# design.net
KiCad netlist of a schematic drawn in Altium Designer
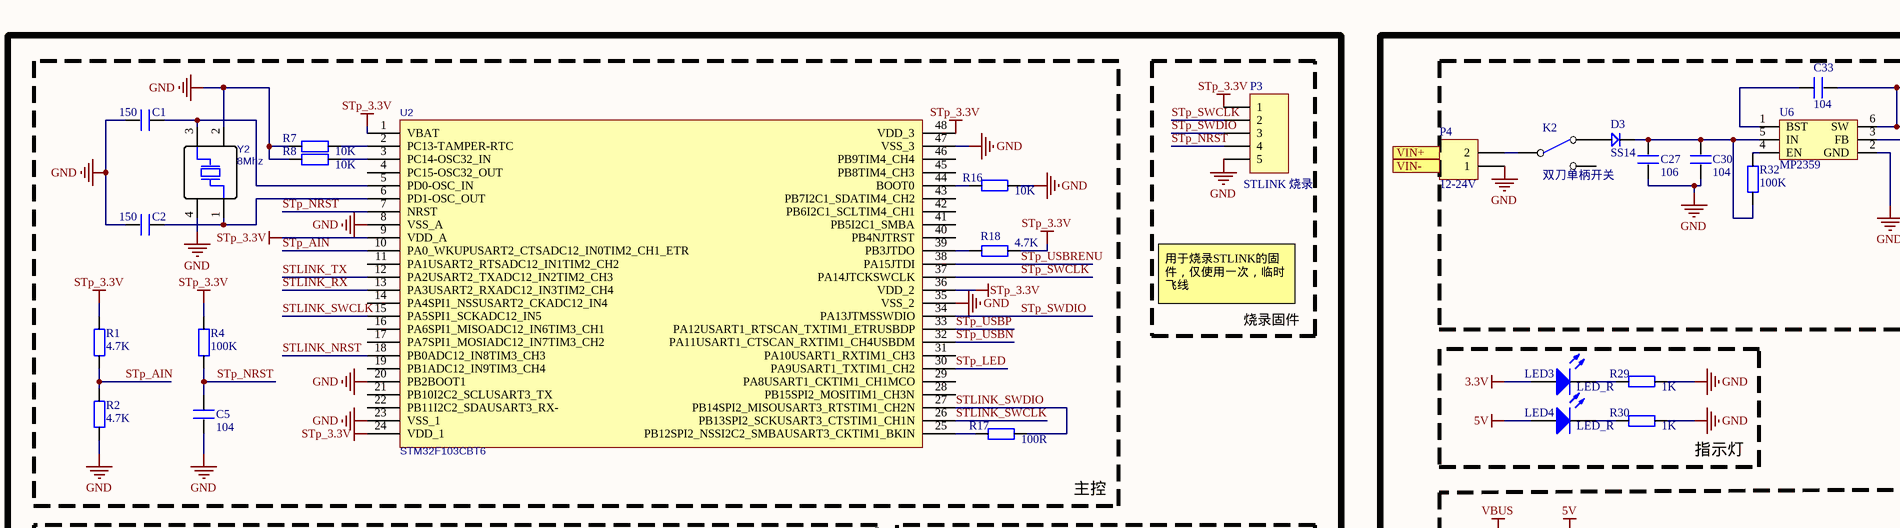
[diagram p0: 主板.SchDoc, top left]
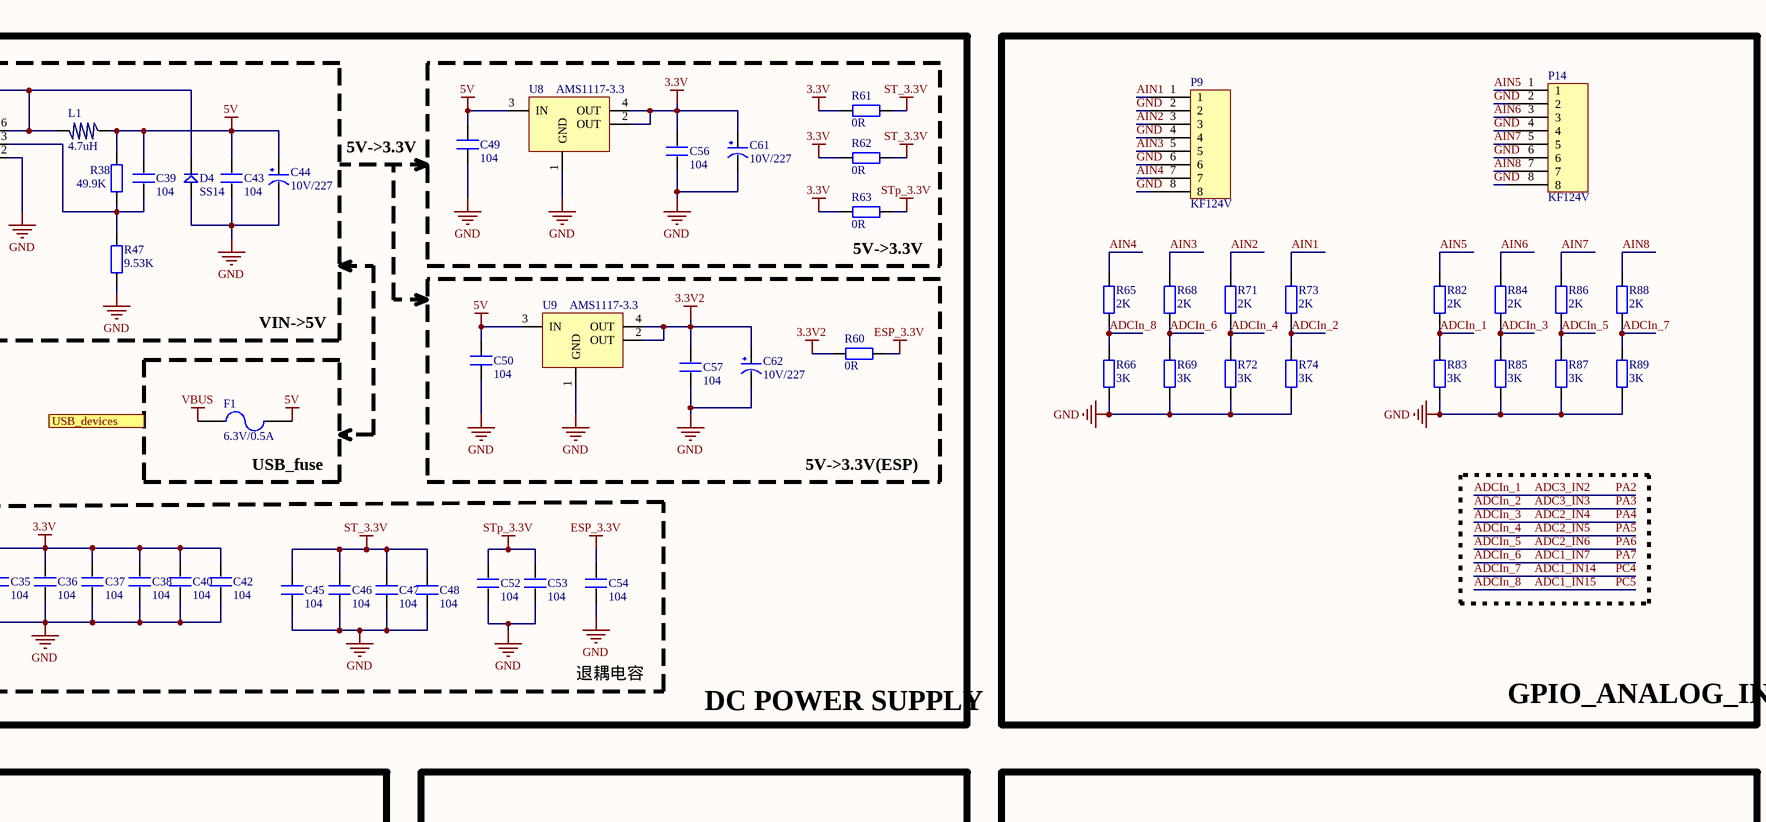
[diagram p1: 主板.SchDoc, top right]
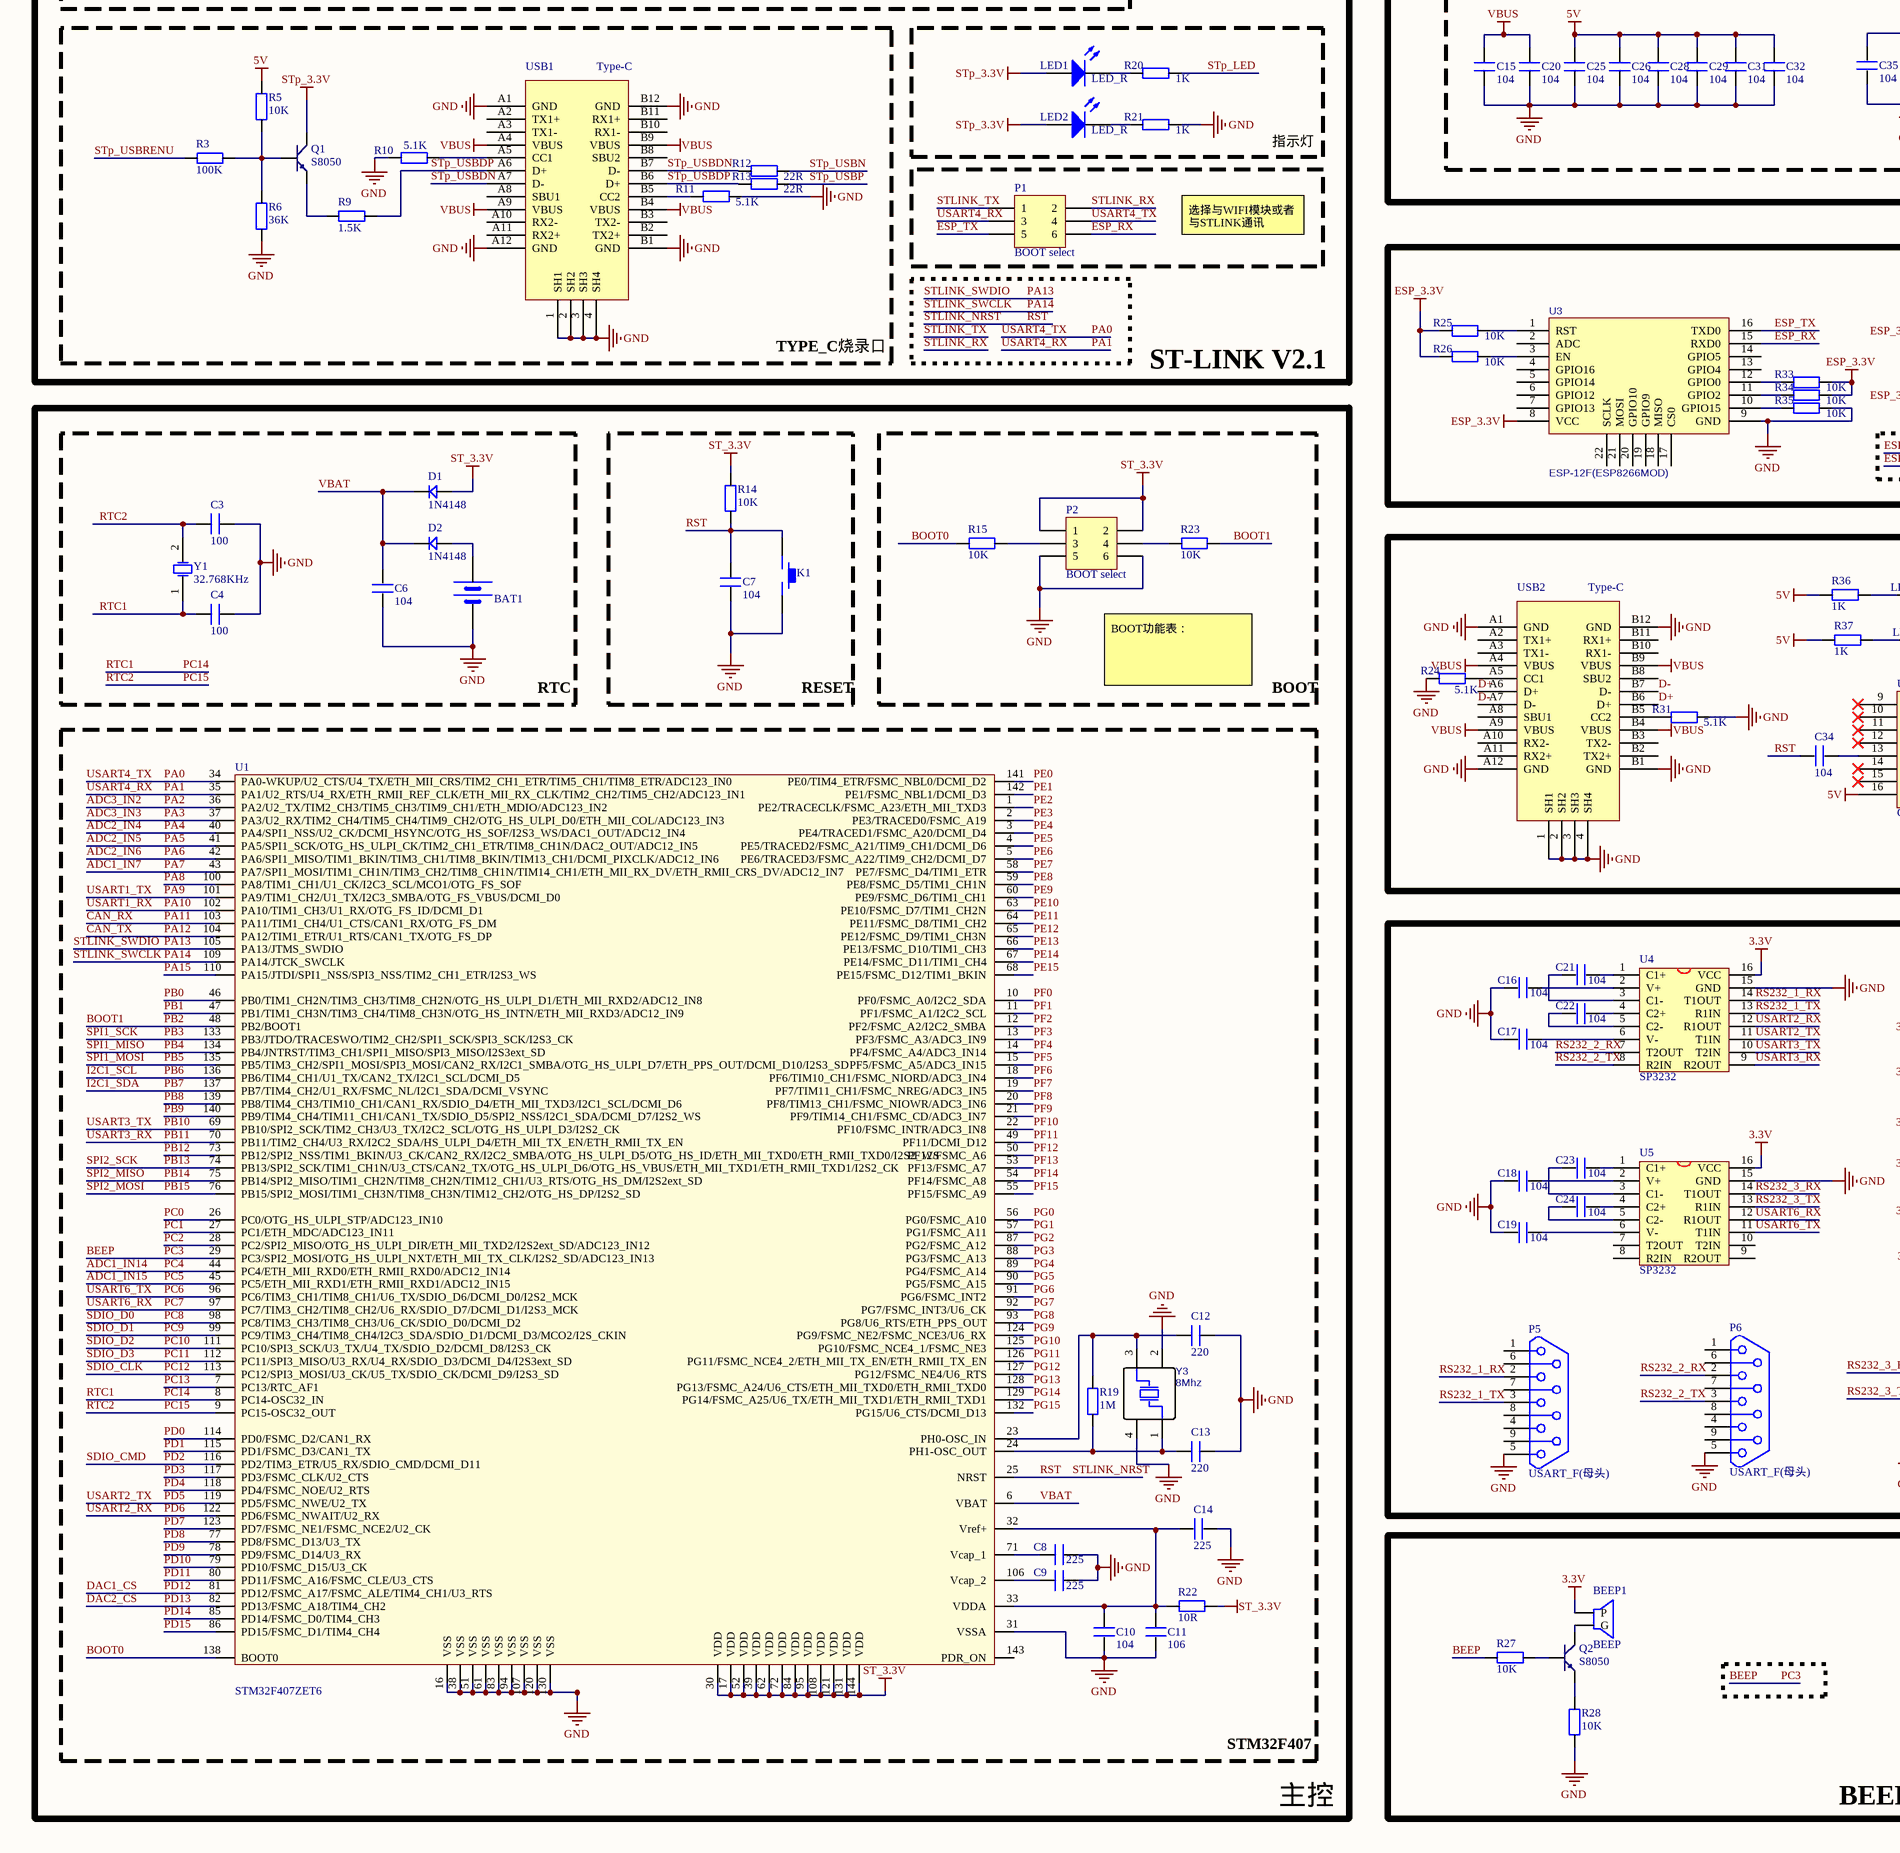
[diagram p2: 主板.SchDoc, bottom left]
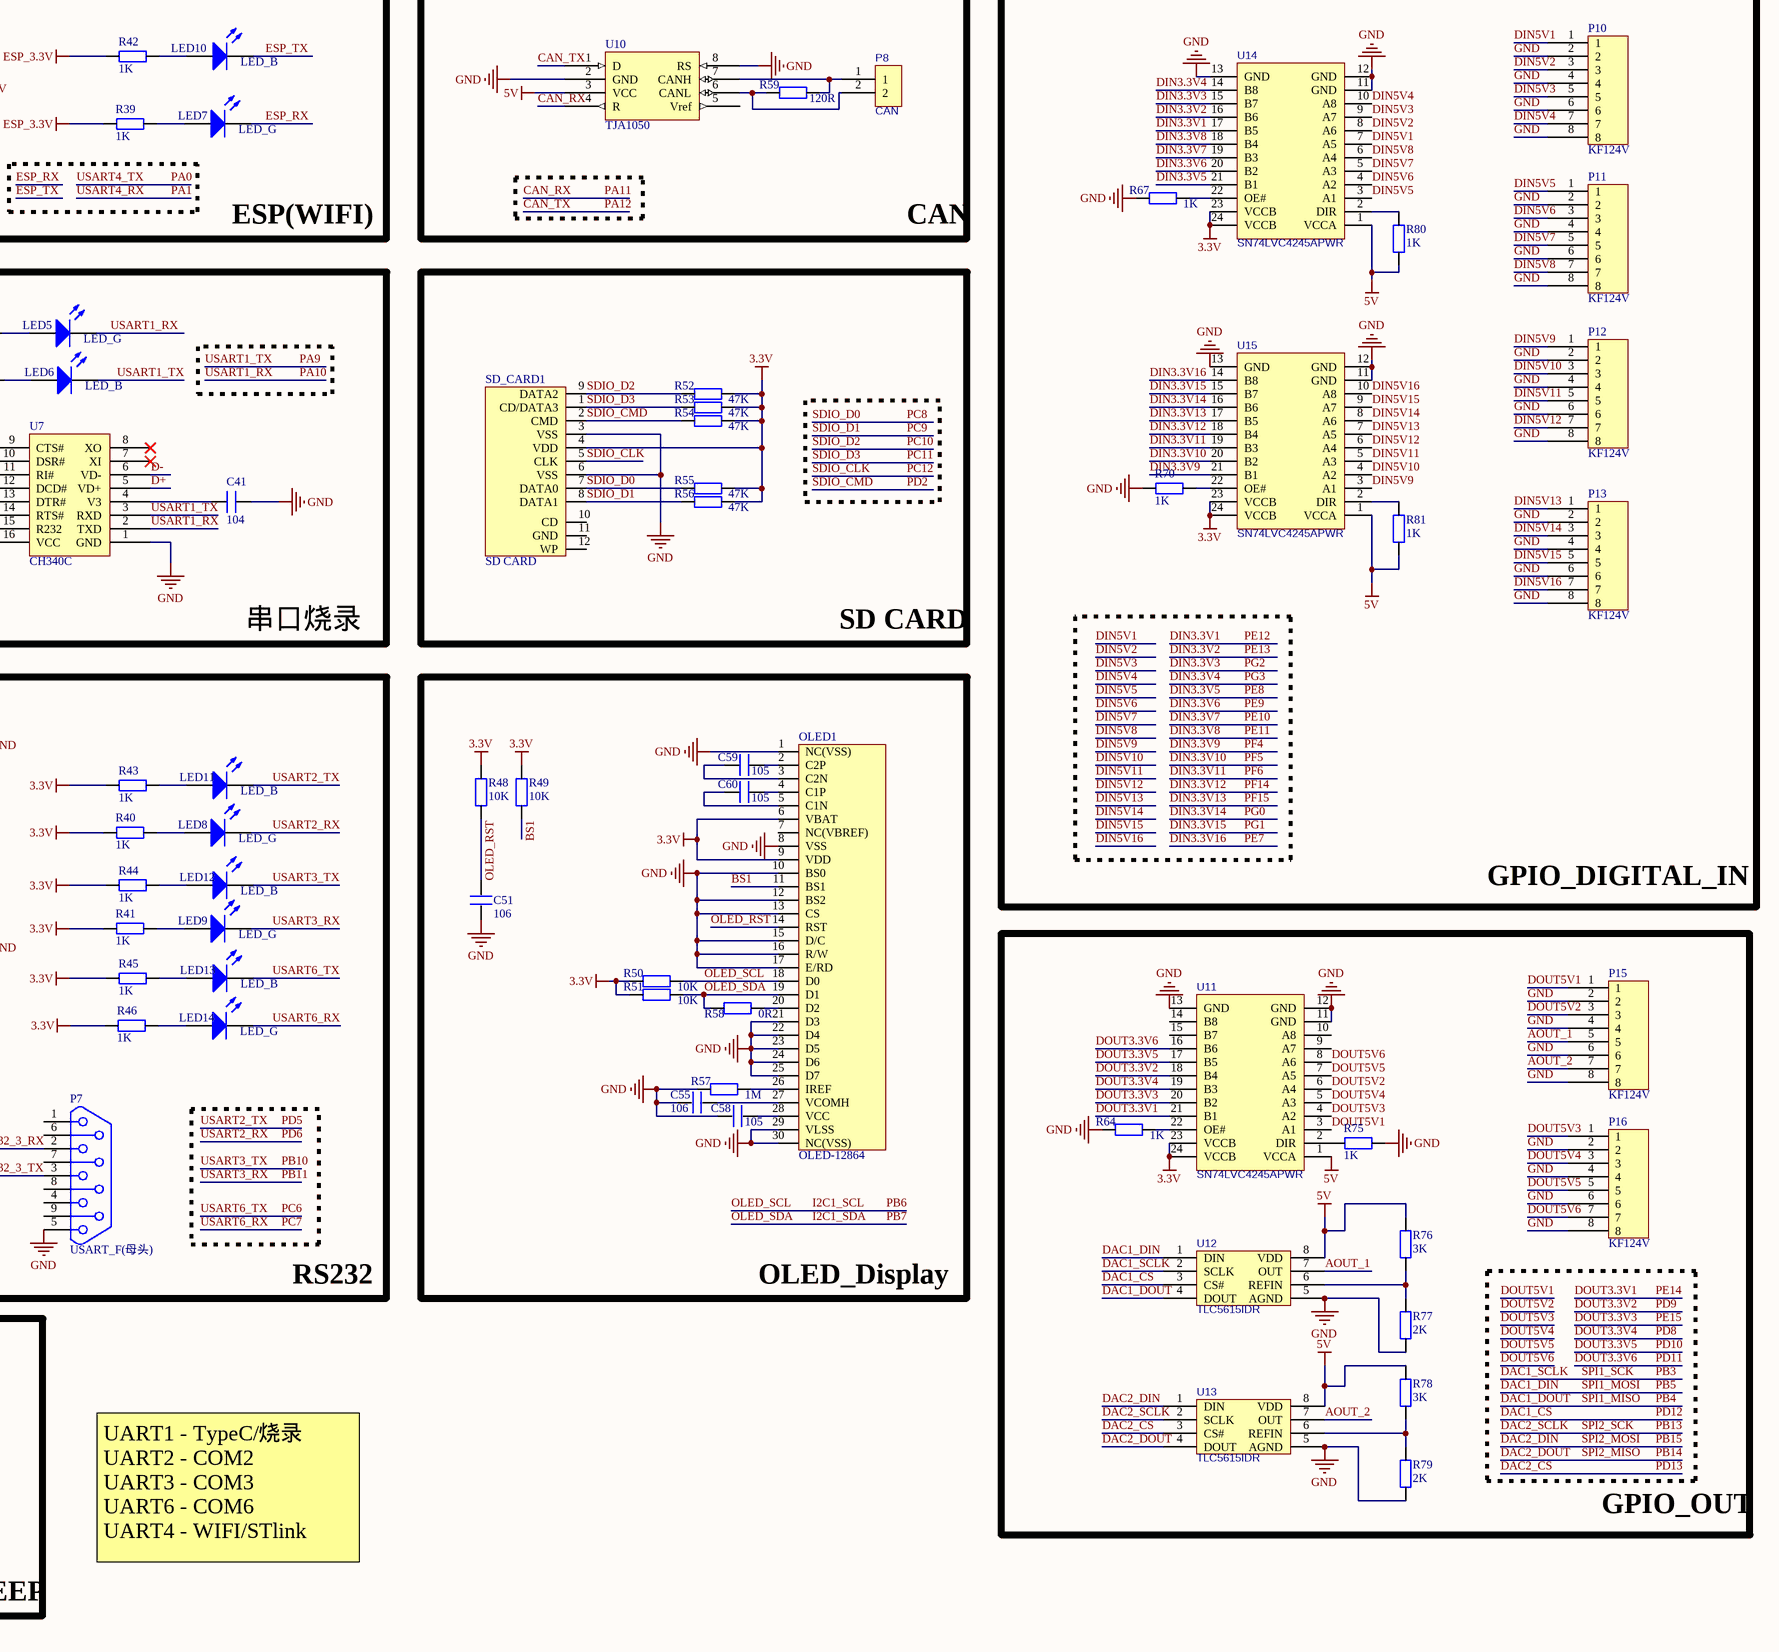
[diagram p3: 主板.SchDoc, bottom right]

(export (version "E")
  (design (tool "Eeschema 10.0.6"))
  (components
    (comp (ref "BAT1") (value "BATT") (footprint "CR1220_B") (libsource (lib "EXPLORER") (part "BAT")))
    (comp (ref "BEEP1") (value "BEEP") (footprint "BEEP 5x9x5.5") (libsource (lib "EXPLORER") (part "BEEP")))
    (comp (ref "C1") (value "150") (footprint "C 0805_L") (libsource (lib "EXPLORER") (part "C")))
    (comp (ref "C2") (value "150") (footprint "C 0805_L") (libsource (lib "EXPLORER") (part "C")))
    (comp (ref "C3") (value "100") (footprint "C 0805_L") (libsource (lib "EXPLORER") (part "C")))
    (comp (ref "C4") (value "100") (footprint "C 0805_L") (libsource (lib "EXPLORER") (part "C")))
    (comp (ref "C5") (value "104") (footprint "C 0805_L") (libsource (lib "EXPLORER") (part "C")))
    (comp (ref "C6") (value "104") (footprint "C 0805_L") (libsource (lib "EXPLORER") (part "C")))
    (comp (ref "C7") (value "104") (footprint "C 0805_L") (libsource (lib "EXPLORER") (part "C")))
    (comp (ref "C8") (value "225") (footprint "C 0805_L") (libsource (lib "EXPLORER") (part "C")))
    (comp (ref "C9") (value "225") (footprint "C 0805_L") (libsource (lib "EXPLORER") (part "C")))
    (comp (ref "C10") (value "104") (footprint "C 0805_L") (libsource (lib "EXPLORER") (part "C")))
    (comp (ref "C11") (value "106") (footprint "C 0805_L") (libsource (lib "EXPLORER") (part "C")))
    (comp (ref "C12") (value "220") (footprint "C 0805_L") (libsource (lib "EXPLORER") (part "C")))
    (comp (ref "C13") (value "220") (footprint "C 0805_L") (libsource (lib "EXPLORER") (part "C")))
    (comp (ref "C14") (value "225") (footprint "C 0805_L") (libsource (lib "EXPLORER") (part "C")))
    (comp (ref "C15") (value "104") (footprint "C 0805_L") (libsource (lib "EXPLORER") (part "C")))
    (comp (ref "C16") (value "104") (footprint "C 0805_L") (libsource (lib "EXPLORER") (part "C")))
    (comp (ref "C17") (value "104") (footprint "C 0805_L") (libsource (lib "EXPLORER") (part "C")))
    (comp (ref "C18") (value "104") (footprint "C 0805_L") (libsource (lib "EXPLORER") (part "C")))
    (comp (ref "C19") (value "104") (footprint "C 0805_L") (libsource (lib "EXPLORER") (part "C")))
    (comp (ref "C20") (value "104") (footprint "C 0805_L") (libsource (lib "EXPLORER") (part "C")))
    (comp (ref "C21") (value "104") (footprint "C 0805_L") (libsource (lib "EXPLORER") (part "C")))
    (comp (ref "C22") (value "104") (footprint "C 0805_L") (libsource (lib "EXPLORER") (part "C")))
    (comp (ref "C23") (value "104") (footprint "C 0805_L") (libsource (lib "EXPLORER") (part "C")))
    (comp (ref "C24") (value "104") (footprint "C 0805_L") (libsource (lib "EXPLORER") (part "C")))
    (comp (ref "C25") (value "104") (footprint "C 0805_L") (libsource (lib "EXPLORER") (part "C")))
    (comp (ref "C26") (value "104") (footprint "C 0805_L") (libsource (lib "EXPLORER") (part "C")))
    (comp (ref "C27") (value "106") (footprint "C 1206_L") (libsource (lib "EXPLORER") (part "C")))
    (comp (ref "C28") (value "104") (footprint "C 0805_L") (libsource (lib "EXPLORER") (part "C")))
    (comp (ref "C29") (value "104") (footprint "C 0805_L") (libsource (lib "EXPLORER") (part "C")))
    (comp (ref "C30") (value "104") (footprint "C 0805_L") (libsource (lib "EXPLORER") (part "C")))
    (comp (ref "C31") (value "104") (footprint "C 0805_L") (libsource (lib "EXPLORER") (part "C")))
    (comp (ref "C32") (value "104") (footprint "C 0805_L") (libsource (lib "EXPLORER") (part "C")))
    (comp (ref "C33") (value "104") (footprint "C 0805_L") (libsource (lib "EXPLORER") (part "C")))
    (comp (ref "C34")
      (value "104")
      (footprint "C 0805_L")
      (description "（可去）")
      (libsource (lib "EXPLORER") (part "C"))
    )
    (comp (ref "C35") (value "104") (footprint "C 0805_L") (libsource (lib "EXPLORER") (part "C")))
    (comp (ref "C36") (value "104") (footprint "C 0805_L") (libsource (lib "EXPLORER") (part "C")))
    (comp (ref "C37") (value "104") (footprint "C 0805_L") (libsource (lib "EXPLORER") (part "C")))
    (comp (ref "C38") (value "104") (footprint "C 0805_L") (libsource (lib "EXPLORER") (part "C")))
    (comp (ref "C39") (value "104") (footprint "C 0805_L") (libsource (lib "EXPLORER") (part "C")))
    (comp (ref "C40") (value "104") (footprint "C 0805_L") (libsource (lib "EXPLORER") (part "C")))
    (comp (ref "C41") (value "104") (footprint "C 0805_L") (libsource (lib "EXPLORER") (part "C")))
    (comp (ref "C42") (value "104") (footprint "C 0805_L") (libsource (lib "EXPLORER") (part "C")))
    (comp (ref "C43") (value "104") (footprint "C 0805_L") (libsource (lib "EXPLORER") (part "C")))
    (comp (ref "C44") (value "10V/227") (footprint "CM D(6.3*7.7)") (libsource (lib "EXPLORER") (part "CAP")))
    (comp (ref "C45") (value "104") (footprint "C 0805_L") (libsource (lib "EXPLORER") (part "C")))
    (comp (ref "C46") (value "104") (footprint "C 0805_L") (libsource (lib "EXPLORER") (part "C")))
    (comp (ref "C47") (value "104") (footprint "C 0805_L") (libsource (lib "EXPLORER") (part "C")))
    (comp (ref "C48") (value "104") (footprint "C 0805_L") (libsource (lib "EXPLORER") (part "C")))
    (comp (ref "C49") (value "104") (footprint "C 0805_L") (libsource (lib "EXPLORER") (part "C")))
    (comp (ref "C50") (value "104") (footprint "C 0805_L") (libsource (lib "EXPLORER") (part "C")))
    (comp (ref "C51") (value "106") (footprint "C 0805_L") (libsource (lib "EXPLORER") (part "C")))
    (comp (ref "C52") (value "104") (footprint "C 0805_L") (libsource (lib "EXPLORER") (part "C")))
    (comp (ref "C53") (value "104") (footprint "C 0805_L") (libsource (lib "EXPLORER") (part "C")))
    (comp (ref "C54") (value "104") (footprint "C 0805_L") (libsource (lib "EXPLORER") (part "C")))
    (comp (ref "C55") (value "106") (footprint "C 0805_L") (libsource (lib "EXPLORER") (part "C")))
    (comp (ref "C56") (value "104") (footprint "C 0805_L") (libsource (lib "EXPLORER") (part "C")))
    (comp (ref "C57") (value "104") (footprint "C 0805_L") (libsource (lib "EXPLORER") (part "C")))
    (comp (ref "C58") (value "105") (footprint "C 0805_L") (libsource (lib "EXPLORER") (part "C")))
    (comp (ref "C59") (value "105") (footprint "C 0805_L") (libsource (lib "EXPLORER") (part "C")))
    (comp (ref "C60") (value "105") (footprint "C 0805_L") (libsource (lib "EXPLORER") (part "C")))
    (comp (ref "C61") (value "10V/227") (footprint "CM D(6.3*7.7)") (libsource (lib "EXPLORER") (part "CAP")))
    (comp (ref "C62") (value "10V/227") (footprint "CM D(6.3*7.7)") (libsource (lib "EXPLORER") (part "CAP")))
    (comp (ref "D1") (value "1N4148") (footprint "MINI_MELF (LL34)") (libsource (lib "EXPLORER") (part "D")))
    (comp (ref "D2") (value "1N4148") (footprint "MINI_MELF (LL34)") (libsource (lib "EXPLORER") (part "D")))
    (comp (ref "D3") (value "SS14") (footprint "SMA") (libsource (lib "EXPLORER") (part "D")))
    (comp (ref "D4") (value "SS14") (footprint "SMA") (libsource (lib "EXPLORER") (part "D")))
    (comp (ref "F1")
      (value "6.3V/0.5A")
      (footprint "C 0805_L")
      (description "Fuse")
      (fields (field (name "PUBLISHER") "Altium Limited"))
      (libsource (lib "Miscellaneous Devices") (part "Fuse 2"))
    )
    (comp (ref "K1")
      (value "KEY_M")
      (footprint "TSW SMD-3*6*2.5")
      (libsource (lib "EXPLORER") (part "KEY_M"))
    )
    (comp (ref "K2") (value "双刀单柄开关") (footprint "SS-12D10") (libsource (lib "k-开关") (part "双刀单柄开关")))
    (comp (ref "L1") (value "4.7uH") (footprint "CDRH74") (libsource (lib "EXPLORER") (part "L")))
    (comp (ref "LED1")
      (value "LED_R")
      (footprint "LED 0805R")
      (description "Typical RED, GREEN, YELLOW, AMBER GaAs LED")
      (fields (field (name "PUBLISHER") "Altium Limited"))
      (libsource (lib "EXPLORER") (part "LED"))
    )
    (comp (ref "LED2")
      (value "LED_R")
      (footprint "LED 0805R")
      (description "Typical RED, GREEN, YELLOW, AMBER GaAs LED")
      (fields (field (name "PUBLISHER") "Altium Limited"))
      (libsource (lib "EXPLORER") (part "LED"))
    )
    (comp (ref "LED3")
      (value "LED_R")
      (footprint "LED 0805R")
      (description "Typical RED, GREEN, YELLOW, AMBER GaAs LED")
      (fields (field (name "PUBLISHER") "Altium Limited"))
      (libsource (lib "EXPLORER") (part "LED"))
    )
    (comp (ref "LED4")
      (value "LED_R")
      (footprint "LED 0805R")
      (description "Typical RED, GREEN, YELLOW, AMBER GaAs LED")
      (fields (field (name "PUBLISHER") "Altium Limited"))
      (libsource (lib "EXPLORER") (part "LED"))
    )
    (comp (ref "LED5")
      (value "LED_G")
      (footprint "LED 0805G")
      (description "Typical RED, GREEN, YELLOW, AMBER GaAs LED")
      (fields (field (name "PUBLISHER") "Altium Limited"))
      (libsource (lib "EXPLORER") (part "LED"))
    )
    (comp (ref "LED6")
      (value "LED_B")
      (footprint "LED 0805B")
      (description "Typical RED, GREEN, YELLOW, AMBER GaAs LED")
      (fields (field (name "PUBLISHER") "Altium Limited"))
      (libsource (lib "EXPLORER") (part "LED"))
    )
    (comp (ref "LED7")
      (value "LED_G")
      (footprint "LED 0805G")
      (description "Typical RED, GREEN, YELLOW, AMBER GaAs LED")
      (fields (field (name "PUBLISHER") "Altium Limited"))
      (libsource (lib "EXPLORER") (part "LED"))
    )
    (comp (ref "LED8")
      (value "LED_G")
      (footprint "LED 0805G")
      (description "Typical RED, GREEN, YELLOW, AMBER GaAs LED")
      (fields (field (name "PUBLISHER") "Altium Limited"))
      (libsource (lib "EXPLORER") (part "LED"))
    )
    (comp (ref "LED9")
      (value "LED_G")
      (footprint "LED 0805G")
      (description "Typical RED, GREEN, YELLOW, AMBER GaAs LED")
      (fields (field (name "PUBLISHER") "Altium Limited"))
      (libsource (lib "EXPLORER") (part "LED"))
    )
    (comp (ref "LED10")
      (value "LED_B")
      (footprint "LED 0805B")
      (description "Typical RED, GREEN, YELLOW, AMBER GaAs LED")
      (fields (field (name "PUBLISHER") "Altium Limited"))
      (libsource (lib "EXPLORER") (part "LED"))
    )
    (comp (ref "LED11")
      (value "LED_B")
      (footprint "LED 0805B")
      (description "Typical RED, GREEN, YELLOW, AMBER GaAs LED")
      (fields (field (name "PUBLISHER") "Altium Limited"))
      (libsource (lib "EXPLORER") (part "LED"))
    )
    (comp (ref "LED12")
      (value "LED_B")
      (footprint "LED 0805B")
      (description "Typical RED, GREEN, YELLOW, AMBER GaAs LED")
      (fields (field (name "PUBLISHER") "Altium Limited"))
      (libsource (lib "EXPLORER") (part "LED"))
    )
    (comp (ref "LED13")
      (value "LED_B")
      (footprint "LED 0805B")
      (description "Typical RED, GREEN, YELLOW, AMBER GaAs LED")
      (fields (field (name "PUBLISHER") "Altium Limited"))
      (libsource (lib "EXPLORER") (part "LED"))
    )
    (comp (ref "LED14")
      (value "LED_G")
      (footprint "LED 0805G")
      (description "Typical RED, GREEN, YELLOW, AMBER GaAs LED")
      (fields (field (name "PUBLISHER") "Altium Limited"))
      (libsource (lib "EXPLORER") (part "LED"))
    )
    (comp (ref "OLED1")
      (value "OLED-12864")
      (footprint "OLED-12864-1.3-TOP")
      (description "显示屏")
      (libsource (lib "EXPLORER") (part "OLED-12864"))
    )
    (comp (ref "P1")
      (value "BOOT select")
      (footprint "HDR2.54-LI-2x3P")
      (description "Header, 3-Pin, Dual row")
      (fields (field (name "PUBLISHER") "Altium Limited"))
      (libsource (lib "EXPLORER") (part "Header 3X2"))
    )
    (comp (ref "P2")
      (value "BOOT select")
      (footprint "HDR2.54-LI-2x3P")
      (description "Header, 3-Pin, Dual row")
      (fields (field (name "PUBLISHER") "Altium Limited"))
      (libsource (lib "EXPLORER") (part "Header 3X2"))
    )
    (comp (ref "P3")
      (value "STLINK 烧录")
      (footprint "ISP5")
      (description "Header, 5-Pin")
      (fields (field (name "PUBLISHER") "Altium Limited"))
      (libsource (lib "主板") (part "Header 5"))
    )
    (comp (ref "P4")
      (value "12-24V")
      (footprint "KF128-5.08-2P")
      (fields (field (name "PUBLISHER") "Altium Limited"))
      (libsource (lib "EXPLORER") (part "Header 2"))
    )
    (comp (ref "P5") (value "USART_F(母头)") (footprint "DB9/S_A") (libsource (lib "EXPLORER") (part "DB9母头")))
    (comp (ref "P6") (value "USART_F(母头)") (footprint "DB9/S_A") (libsource (lib "EXPLORER") (part "DB9母头")))
    (comp (ref "P7") (value "USART_F(母头)") (footprint "DB9/S_A") (libsource (lib "EXPLORER") (part "DB9母头")))
    (comp (ref "P8")
      (value "CAN")
      (footprint "KF142V-5.08-2P")
      (fields
        (field (name "BOM_SUPPLIER PART") "C475134")
        (field (name "BOM_MANUFACTURER PART") "KF142V-5.08-2P")
        (field (name "CONTRIBUTOR") "LCSC")
      )
      (libsource (lib "EXPLORER") (part "KF142V-2P"))
    )
    (comp (ref "P9") (value "KF124V") (footprint "KF142V-5.08-8P") (libsource (lib "EXPLORER") (part "KF8P")))
    (comp (ref "P10")
      (value "KF124V")
      (footprint "KF142V-5.08-8P")
      (libsource (lib "EXPLORER") (part "KF142V-8P"))
    )
    (comp (ref "P11")
      (value "KF124V")
      (footprint "KF142V-5.08-8P")
      (libsource (lib "EXPLORER") (part "KF142V-8P"))
    )
    (comp (ref "P12")
      (value "KF124V")
      (footprint "KF142V-5.08-8P")
      (libsource (lib "EXPLORER") (part "KF142V-8P"))
    )
    (comp (ref "P13")
      (value "KF124V")
      (footprint "KF142V-5.08-8P")
      (libsource (lib "EXPLORER") (part "KF142V-8P"))
    )
    (comp (ref "P14")
      (value "KF124V")
      (footprint "KF142V-5.08-8P")
      (libsource (lib "EXPLORER") (part "KF142V-8P"))
    )
    (comp (ref "P15")
      (value "KF124V")
      (footprint "KF142V-5.08-8P")
      (libsource (lib "EXPLORER") (part "KF142V-8P"))
    )
    (comp (ref "P16")
      (value "KF124V")
      (footprint "KF142V-5.08-8P")
      (libsource (lib "EXPLORER") (part "KF142V-8P"))
    )
    (comp (ref "Q1")
      (value "S8050")
      (footprint "SOT23-3L")
      (description "8050/BCW846/BCW847")
      (libsource (lib "EXPLORER") (part "NPN"))
    )
    (comp (ref "Q2")
      (value "S8050")
      (footprint "SOT23-3L")
      (description "8050/BCW846/BCW847")
      (libsource (lib "EXPLORER") (part "NPN"))
    )
    (comp (ref "R1") (value "4.7K") (footprint "R 0805_L") (libsource (lib "EXPLORER") (part "R")))
    (comp (ref "R2") (value "4.7K") (footprint "R 0805_L") (libsource (lib "EXPLORER") (part "R")))
    (comp (ref "R3") (value "100K") (footprint "R 0805_L") (libsource (lib "EXPLORER") (part "R")))
    (comp (ref "R4") (value "100K") (footprint "R 0805_L") (libsource (lib "EXPLORER") (part "R")))
    (comp (ref "R5") (value "10K") (footprint "R 0805_L") (libsource (lib "EXPLORER") (part "R")))
    (comp (ref "R6") (value "36K") (footprint "R 0805_L") (libsource (lib "EXPLORER") (part "R")))
    (comp (ref "R7") (value "10K") (footprint "R 0805_L") (libsource (lib "EXPLORER") (part "R")))
    (comp (ref "R8") (value "10K") (footprint "R 0805_L") (libsource (lib "EXPLORER") (part "R")))
    (comp (ref "R9") (value "1.5K") (footprint "R 0805_L") (libsource (lib "EXPLORER") (part "R")))
    (comp (ref "R10") (value "5.1K") (footprint "R 0805_L") (libsource (lib "EXPLORER") (part "R")))
    (comp (ref "R11") (value "5.1K") (footprint "R 0805_L") (libsource (lib "EXPLORER") (part "R")))
    (comp (ref "R12") (value "22R") (footprint "R 0805_L") (libsource (lib "EXPLORER") (part "R")))
    (comp (ref "R13") (value "22R") (footprint "R 0805_L") (libsource (lib "EXPLORER") (part "R")))
    (comp (ref "R14") (value "10K") (footprint "R 0805_L") (libsource (lib "EXPLORER") (part "R")))
    (comp (ref "R15") (value "10K") (footprint "R 0805_L") (libsource (lib "EXPLORER") (part "R")))
    (comp (ref "R16") (value "10K") (footprint "R 0805_L") (libsource (lib "EXPLORER") (part "R")))
    (comp (ref "R17") (value "100R") (footprint "R 0805_L") (libsource (lib "EXPLORER") (part "R")))
    (comp (ref "R18") (value "4.7K") (footprint "R 0805_L") (libsource (lib "EXPLORER") (part "R")))
    (comp (ref "R19") (value "1M") (footprint "R 0805_L") (libsource (lib "EXPLORER") (part "R")))
    (comp (ref "R20") (value "1K") (footprint "R 0805_L") (libsource (lib "EXPLORER") (part "R")))
    (comp (ref "R21") (value "1K") (footprint "R 0805_L") (libsource (lib "EXPLORER") (part "R")))
    (comp (ref "R22") (value "10R") (footprint "R 0805_L") (libsource (lib "EXPLORER") (part "R")))
    (comp (ref "R23") (value "10K") (footprint "R 0805_L") (libsource (lib "EXPLORER") (part "R")))
    (comp (ref "R24") (value "5.1K") (footprint "R 0805_L") (libsource (lib "EXPLORER") (part "R")))
    (comp (ref "R25") (value "10K") (footprint "R 0805_L") (libsource (lib "EXPLORER") (part "R")))
    (comp (ref "R26") (value "10K") (footprint "R 0805_L") (libsource (lib "EXPLORER") (part "R")))
    (comp (ref "R27") (value "10K") (footprint "R 0805_L") (libsource (lib "EXPLORER") (part "R")))
    (comp (ref "R28") (value "10K") (footprint "R 0805_L") (libsource (lib "EXPLORER") (part "R")))
    (comp (ref "R29") (value "1K") (footprint "R 0805_L") (libsource (lib "EXPLORER") (part "R")))
    (comp (ref "R30") (value "1K") (footprint "R 0805_L") (libsource (lib "EXPLORER") (part "R")))
    (comp (ref "R31") (value "5.1K") (footprint "R 0805_L") (libsource (lib "EXPLORER") (part "R")))
    (comp (ref "R32") (value "100K") (footprint "R 0805_L") (libsource (lib "EXPLORER") (part "R")))
    (comp (ref "R33") (value "10K") (footprint "R 0805_L") (libsource (lib "EXPLORER") (part "R")))
    (comp (ref "R34") (value "10K") (footprint "R 0805_L") (libsource (lib "EXPLORER") (part "R")))
    (comp (ref "R35") (value "10K") (footprint "R 0805_L") (libsource (lib "EXPLORER") (part "R")))
    (comp (ref "R36") (value "1K") (footprint "R 0805_L") (libsource (lib "EXPLORER") (part "R")))
    (comp (ref "R37") (value "1K") (footprint "R 0805_L") (libsource (lib "EXPLORER") (part "R")))
    (comp (ref "R38") (value "49.9K") (footprint "R 0805_L") (libsource (lib "EXPLORER") (part "R")))
    (comp (ref "R39") (value "1K") (footprint "R 0805_L") (libsource (lib "EXPLORER") (part "R")))
    (comp (ref "R40") (value "1K") (footprint "R 0805_L") (libsource (lib "EXPLORER") (part "R")))
    (comp (ref "R41") (value "1K") (footprint "R 0805_L") (libsource (lib "EXPLORER") (part "R")))
    (comp (ref "R42") (value "1K") (footprint "R 0805_L") (libsource (lib "EXPLORER") (part "R")))
    (comp (ref "R43") (value "1K") (footprint "R 0805_L") (libsource (lib "EXPLORER") (part "R")))
    (comp (ref "R44") (value "1K") (footprint "R 0805_L") (libsource (lib "EXPLORER") (part "R")))
    (comp (ref "R45") (value "1K") (footprint "R 0805_L") (libsource (lib "EXPLORER") (part "R")))
    (comp (ref "R46") (value "1K") (footprint "R 0805_L") (libsource (lib "EXPLORER") (part "R")))
    (comp (ref "R47") (value "9.53K") (footprint "R 0805_L") (libsource (lib "EXPLORER") (part "R")))
    (comp (ref "R48") (value "10K") (footprint "R 0805_L") (libsource (lib "EXPLORER") (part "R")))
    (comp (ref "R49") (value "10K") (footprint "R 0805_L") (libsource (lib "EXPLORER") (part "R")))
    (comp (ref "R50") (value "10K") (footprint "R 0805_L") (libsource (lib "EXPLORER") (part "R")))
    (comp (ref "R51") (value "10K") (footprint "R 0805_L") (libsource (lib "EXPLORER") (part "R")))
    (comp (ref "R52") (value "47K") (footprint "R 0805_L") (libsource (lib "EXPLORER") (part "R")))
    (comp (ref "R53") (value "47K") (footprint "R 0805_L") (libsource (lib "EXPLORER") (part "R")))
    (comp (ref "R54") (value "47K") (footprint "R 0805_L") (libsource (lib "EXPLORER") (part "R")))
    (comp (ref "R55") (value "47K") (footprint "R 0805_L") (libsource (lib "EXPLORER") (part "R")))
    (comp (ref "R56") (value "47K") (footprint "R 0805_L") (libsource (lib "EXPLORER") (part "R")))
    (comp (ref "R57") (value "1M") (footprint "R 0805_L") (libsource (lib "EXPLORER") (part "R")))
    (comp (ref "R58") (value "0R") (footprint "R 0805_L") (libsource (lib "EXPLORER") (part "R")))
    (comp (ref "R59") (value "120R") (footprint "R 0805_L") (libsource (lib "EXPLORER") (part "R")))
    (comp (ref "R60") (value "0R") (footprint "R 0805_L") (libsource (lib "EXPLORER") (part "R")))
    (comp (ref "R61") (value "0R") (footprint "R 0805_L") (libsource (lib "EXPLORER") (part "R")))
    (comp (ref "R62") (value "0R") (footprint "R 0805_L") (libsource (lib "EXPLORER") (part "R")))
    (comp (ref "R63") (value "0R") (footprint "R 0805_L") (libsource (lib "EXPLORER") (part "R")))
    (comp (ref "R64") (value "1K") (footprint "R 0805_L") (libsource (lib "EXPLORER") (part "R")))
    (comp (ref "R65") (value "2K") (footprint "R 0805_L") (libsource (lib "EXPLORER") (part "R")))
    (comp (ref "R66") (value "3K") (footprint "R 0805_L") (libsource (lib "EXPLORER") (part "R")))
    (comp (ref "R67") (value "1K") (footprint "R 0805_L") (libsource (lib "EXPLORER") (part "R")))
    (comp (ref "R68") (value "2K") (footprint "R 0805_L") (libsource (lib "EXPLORER") (part "R")))
    (comp (ref "R69") (value "3K") (footprint "R 0805_L") (libsource (lib "EXPLORER") (part "R")))
    (comp (ref "R70") (value "1K") (footprint "R 0805_L") (libsource (lib "EXPLORER") (part "R")))
    (comp (ref "R71") (value "2K") (footprint "R 0805_L") (libsource (lib "EXPLORER") (part "R")))
    (comp (ref "R72") (value "3K") (footprint "R 0805_L") (libsource (lib "EXPLORER") (part "R")))
    (comp (ref "R73") (value "2K") (footprint "R 0805_L") (libsource (lib "EXPLORER") (part "R")))
    (comp (ref "R74") (value "3K") (footprint "R 0805_L") (libsource (lib "EXPLORER") (part "R")))
    (comp (ref "R75") (value "1K") (footprint "R 0805_L") (libsource (lib "EXPLORER") (part "R")))
    (comp (ref "R76") (value "3K") (footprint "R 0805_L") (libsource (lib "EXPLORER") (part "R")))
    (comp (ref "R77") (value "2K") (footprint "R 0805_L") (libsource (lib "EXPLORER") (part "R")))
    (comp (ref "R78") (value "3K") (footprint "R 0805_L") (libsource (lib "EXPLORER") (part "R")))
    (comp (ref "R79") (value "2K") (footprint "R 0805_L") (libsource (lib "EXPLORER") (part "R")))
    (comp (ref "R80") (value "1K") (footprint "R 0805_L") (libsource (lib "EXPLORER") (part "R")))
    (comp (ref "R81") (value "1K") (footprint "R 0805_L") (libsource (lib "EXPLORER") (part "R")))
    (comp (ref "R82") (value "2K") (footprint "R 0805_L") (libsource (lib "EXPLORER") (part "R")))
    (comp (ref "R83") (value "3K") (footprint "R 0805_L") (libsource (lib "EXPLORER") (part "R")))
    (comp (ref "R84") (value "2K") (footprint "R 0805_L") (libsource (lib "EXPLORER") (part "R")))
    (comp (ref "R85") (value "3K") (footprint "R 0805_L") (libsource (lib "EXPLORER") (part "R")))
    (comp (ref "R86") (value "2K") (footprint "R 0805_L") (libsource (lib "EXPLORER") (part "R")))
    (comp (ref "R87") (value "3K") (footprint "R 0805_L") (libsource (lib "EXPLORER") (part "R")))
    (comp (ref "R88") (value "2K") (footprint "R 0805_L") (libsource (lib "EXPLORER") (part "R")))
    (comp (ref "R89") (value "3K") (footprint "R 0805_L") (libsource (lib "EXPLORER") (part "R")))
    (comp (ref "SD_CARD1")
      (value "SD CARD")
      (footprint "SD-SMD")
      (libsource (lib "EXPLORER") (part "SD CARD"))
    )
    (comp (ref "U1")
      (value "STM32F407ZET6")
      (footprint "LQFP144 20X20_L")
      (libsource (lib "EXPLORER") (part "STM32F407ZET6"))
    )
    (comp (ref "U2")
      (value "STM32F103CBT6")
      (footprint "TQFP48 7x7_L")
      (fields (field (name "BOM_SUPPLIER PART") "C8304"))
      (libsource (lib "EXPLORER") (part "STM32F103CBT6"))
    )
    (comp (ref "U3")
      (value "ESP-12F(ESP8266MOD)")
      (footprint "ESP32")
      (fields (field (name "BOM_SUPPLIER PART") "C82891"))
      (libsource (lib "EXPLORER") (part "ESP-12F"))
    )
    (comp (ref "U4") (value "SP3232") (footprint "SOP16_L") (libsource (lib "EXPLORER") (part "MAX3232")))
    (comp (ref "U5") (value "SP3232") (footprint "SOP16_L") (libsource (lib "EXPLORER") (part "MAX3232")))
    (comp (ref "U6")
      (value "MP2359")
      (footprint "SOT23-6L")
      (description "DC DC Step Down IC")
      (libsource (lib "EXPLORER") (part "MP2359"))
    )
    (comp (ref "U7") (value "CH340C") (footprint "SOP16_L") (libsource (lib "Schlib1") (part "CH340G")))
    (comp (ref "U8")
      (value "AMS1117-3.3")
      (footprint "SOT223_L")
      (libsource (lib "EXPLORER") (part "AMS1117"))
    )
    (comp (ref "U9")
      (value "AMS1117-3.3")
      (footprint "SOT223_L")
      (libsource (lib "EXPLORER") (part "AMS1117"))
    )
    (comp (ref "U10")
      (value "TJA1050")
      (footprint "SOIC-8")
      (libsource (lib "EXPLORER") (part "SN65HVD230D"))
    )
    (comp (ref "U11")
      (value "SN74LVC4245APWR")
      (footprint "TSSOP24_L")
      (fields (field (name "BOM_SUPPLIER PART") "C7859"))
      (libsource (lib "EXPLORER") (part "SN74LVC4245APWR"))
    )
    (comp (ref "U12")
      (value "TLC5615IDR")
      (footprint "SOIC-8")
      (fields (field (name "BOM_SUPPLIER PART") "C527509") (field (name "CONTRIBUTOR") "LCSC"))
      (libsource (lib "EXPLORER") (part "TLC5615IDR"))
    )
    (comp (ref "U13")
      (value "TLC5615IDR")
      (footprint "SOIC-8")
      (fields (field (name "BOM_SUPPLIER PART") "C527509") (field (name "CONTRIBUTOR") "LCSC"))
      (libsource (lib "EXPLORER") (part "TLC5615IDR"))
    )
    (comp (ref "U14")
      (value "SN74LVC4245APWR")
      (footprint "TSSOP24_L")
      (fields (field (name "BOM_SUPPLIER PART") "C7859"))
      (libsource (lib "EXPLORER") (part "SN74LVC4245APWR"))
    )
    (comp (ref "U15")
      (value "SN74LVC4245APWR")
      (footprint "TSSOP24_L")
      (fields (field (name "BOM_SUPPLIER PART") "C7859"))
      (libsource (lib "EXPLORER") (part "SN74LVC4245APWR"))
    )
    (comp (ref "USB1")
      (value "Type-C")
      (footprint "USBTypeC-16P")
      (libsource (lib "MyPcbLib") (part "USB-Type-C-TOP"))
    )
    (comp (ref "USB2")
      (value "Type-C")
      (footprint "USBTypeC-16P")
      (libsource (lib "MyPcbLib") (part "USB-Type-C-TOP"))
    )
    (comp (ref "Y1")
      (value "32.768KHz")
      (footprint "OSC 3215-2P")
      (description "Crystal Oscillator")
      (fields (field (name "PUBLISHER") "Altium Limited"))
      (libsource (lib "EXPLORER") (part "XTAL"))
    )
    (comp (ref "Y2")
      (value "8Mhz")
      (footprint "OSC 5032-4P")
      (fields
        (field (name "BOM_MANUFACTURER PART") "X322516MLB4SI")
        (field (name "BOM_SUPPLIER PART") "C13738")
      )
      (libsource (lib "EXPLORER") (part "Y"))
    )
    (comp (ref "Y3")
      (value "8Mhz")
      (footprint "OSC 5032-4P")
      (fields
        (field (name "BOM_MANUFACTURER PART") "X322516MLB4SI")
        (field (name "BOM_SUPPLIER PART") "C13738")
      )
      (libsource (lib "EXPLORER") (part "Y"))
    )
  )
  (nets
    (net (code "1") (name "/ADC1_IN7") (class "Default")
      (node (ref "R68") (pin "1") (pintype "passive"))
      (node (ref "R69") (pin "2") (pintype "passive"))
      (node (ref "U1") (pin "43") (pinfunction "PA7/SPI1_MOSI/TIM1_CH1N/TIM3_CH2/TIM8_CH1N/TIM14_CH1/ETH_MII_RX_DV/ETH_RMII_CRS_DV/ADC12_IN7_43") (pintype "passive"))
    )
    (net (code "2") (name "/ADC1_IN14") (class "Default")
      (node (ref "R88") (pin "1") (pintype "passive"))
      (node (ref "R89") (pin "2") (pintype "passive"))
      (node (ref "U1") (pin "44") (pinfunction "PC4/ETH_MII_RXD0/ETH_RMII_RXD0/ADC12_IN14_44") (pintype "passive"))
    )
    (net (code "3") (name "/ADC1_IN15") (class "Default")
      (node (ref "R65") (pin "1") (pintype "passive"))
      (node (ref "R66") (pin "2") (pintype "passive"))
      (node (ref "U1") (pin "45") (pinfunction "PC5/ETH_MII_RXD1/ETH_RMII_RXD1/ADC12_IN15_45") (pintype "passive"))
    )
    (net (code "4") (name "/ADC2_IN4") (class "Default")
      (node (ref "R84") (pin "1") (pintype "passive"))
      (node (ref "R85") (pin "2") (pintype "passive"))
      (node (ref "U1") (pin "40") (pinfunction "PA4/SPI1_NSS/U2_CK/DCMI_HSYNC/OTG_HS_SOF/I2S3_WS/DAC1_OUT/ADC12_IN4_40") (pintype "passive"))
    )
    (net (code "5") (name "/ADC2_IN5") (class "Default")
      (node (ref "R71") (pin "1") (pintype "passive"))
      (node (ref "R72") (pin "2") (pintype "passive"))
      (node (ref "U1") (pin "41") (pinfunction "PA5/SPI1_SCK/OTG_HS_ULPI_CK/TIM2_CH1_ETR/TIM8_CH1N/DAC2_OUT/ADC12_IN5_41") (pintype "passive"))
    )
    (net (code "6") (name "/ADC2_IN6") (class "Default")
      (node (ref "R86") (pin "1") (pintype "passive"))
      (node (ref "R87") (pin "2") (pintype "passive"))
      (node (ref "U1") (pin "42") (pinfunction "PA6/SPI1_MISO/TIM1_BKIN/TIM3_CH1/TIM8_BKIN/TIM13_CH1/DCMI_PIXCLK/ADC12_IN6_42") (pintype "passive"))
    )
    (net (code "7") (name "/ADC3_IN2") (class "Default")
      (node (ref "R82") (pin "1") (pintype "passive"))
      (node (ref "R83") (pin "2") (pintype "passive"))
      (node (ref "U1") (pin "36") (pinfunction "PA2/U2_TX/TIM2_CH3/TIM5_CH3/TIM9_CH1/ETH_MDIO/ADC123_IN2_36") (pintype "passive"))
    )
    (net (code "8") (name "/ADC3_IN3") (class "Default")
      (node (ref "R73") (pin "1") (pintype "passive"))
      (node (ref "R74") (pin "2") (pintype "passive"))
      (node (ref "U1") (pin "37") (pinfunction "PA3/U2_RX/TIM2_CH4/TIM5_CH4/TIM9_CH2/OTG_HS_ULPI_D0/ETH_MII_COL/ADC123_IN3_37") (pintype "passive"))
    )
    (net (code "9") (name "/AIN1") (class "Default")
      (node (ref "P9") (pin "1") (pinfunction "1_1") (pintype "passive"))
      (node (ref "R73") (pin "2") (pintype "passive"))
    )
    (net (code "10") (name "/AIN2") (class "Default")
      (node (ref "P9") (pin "3") (pinfunction "3_3") (pintype "passive"))
      (node (ref "R71") (pin "2") (pintype "passive"))
    )
    (net (code "11") (name "/AIN3") (class "Default")
      (node (ref "P9") (pin "5") (pinfunction "5_5") (pintype "passive"))
      (node (ref "R68") (pin "2") (pintype "passive"))
    )
    (net (code "12") (name "/AIN4") (class "Default")
      (node (ref "P9") (pin "7") (pinfunction "7_7") (pintype "passive"))
      (node (ref "R65") (pin "2") (pintype "passive"))
    )
    (net (code "13") (name "/AIN5") (class "Default")
      (node (ref "P14") (pin "1") (pinfunction "1_1") (pintype "passive"))
      (node (ref "R82") (pin "2") (pintype "passive"))
    )
    (net (code "14") (name "/AIN6") (class "Default")
      (node (ref "P14") (pin "3") (pinfunction "3_3") (pintype "passive"))
      (node (ref "R84") (pin "2") (pintype "passive"))
    )
    (net (code "15") (name "/AIN7") (class "Default")
      (node (ref "P14") (pin "5") (pinfunction "5_5") (pintype "passive"))
      (node (ref "R86") (pin "2") (pintype "passive"))
    )
    (net (code "16") (name "/AIN8") (class "Default")
      (node (ref "P14") (pin "7") (pinfunction "7_7") (pintype "passive"))
      (node (ref "R88") (pin "2") (pintype "passive"))
    )
    (net (code "17") (name "/AOUT_1") (class "Default")
      (node (ref "P15") (pin "5") (pinfunction "5_5") (pintype "passive"))
      (node (ref "U12") (pin "7") (pinfunction "OUT_7") (pintype "passive"))
    )
    (net (code "18") (name "/AOUT_2") (class "Default")
      (node (ref "P15") (pin "7") (pinfunction "7_7") (pintype "passive"))
      (node (ref "U13") (pin "7") (pinfunction "OUT_7") (pintype "passive"))
    )
    (net (code "19") (name "/BEEP") (class "Default")
      (node (ref "R27") (pin "2") (pintype "passive"))
      (node (ref "U1") (pin "29") (pinfunction "PC3/SPI2_MOSI/OTG_HS_ULPI_NXT/ETH_MII_TX_CLK/I2S2_SD/ADC123_IN13_29") (pintype "passive"))
    )
    (net (code "20") (name "/BOOT0") (class "Default")
      (node (ref "R15") (pin "1") (pintype "passive"))
      (node (ref "U1") (pin "138") (pinfunction "BOOT0_138") (pintype "passive"))
    )
    (net (code "21") (name "/BOOT1") (class "Default")
      (node (ref "R23") (pin "2") (pintype "passive"))
      (node (ref "U1") (pin "48") (pinfunction "PB2/BOOT1_48") (pintype "passive"))
    )
    (net (code "22") (name "/BS1") (class "Default")
      (node (ref "OLED1") (pin "11") (pinfunction "BS1_11") (pintype "passive"))
      (node (ref "R49") (pin "2") (pintype "passive"))
    )
    (net (code "23") (name "/CAN_RX") (class "Default")
      (node (ref "U1") (pin "103") (pinfunction "PA11/TIM1_CH4/U1_CTS/CAN1_RX/OTG_FS_DM_103") (pintype "passive"))
      (node (ref "U10") (pin "4") (pinfunction "R_4") (pintype "output"))
    )
    (net (code "24") (name "/CAN_TX") (class "Default")
      (node (ref "U1") (pin "104") (pinfunction "PA12/TIM1_ETR/U1_RTS/CAN1_TX/OTG_FS_DP_104") (pintype "passive"))
      (node (ref "U10") (pin "1") (pinfunction "D_1") (pintype "input"))
    )
    (net (code "25") (name "/D+") (class "Default")
      (node (ref "U7") (pin "5") (pinfunction "VD+_5") (pintype "passive"))
      (node (ref "USB2") (pin "A6") (pinfunction "D+_A6") (pintype "passive"))
      (node (ref "USB2") (pin "B6") (pinfunction "D+_B6") (pintype "passive"))
    )
    (net (code "26") (name "/D-") (class "Default")
      (node (ref "U7") (pin "6") (pinfunction "VD-_6") (pintype "passive"))
      (node (ref "USB2") (pin "A7") (pinfunction "D-_A7") (pintype "passive"))
      (node (ref "USB2") (pin "B7") (pinfunction "D-_B7") (pintype "passive"))
    )
    (net (code "27") (name "/DAC1_CS") (class "Default")
      (node (ref "U1") (pin "81") (pinfunction "PD12/FSMC_A17/FSMC_ALE/TIM4_CH1/U3_RTS_81") (pintype "passive"))
      (node (ref "U12") (pin "3") (pinfunction "CS#_3") (pintype "passive"))
    )
    (net (code "28") (name "/DAC1_DIN") (class "Default")
      (node (ref "U1") (pin "135") (pinfunction "PB5/TIM3_CH2/SPI1_MOSI/SPI3_MOSI/CAN2_RX/I2C1_SMBA/OTG_HS_ULPI_D7/ETH_PPS_OUT/DCMI_D10/I2S3_SD_135") (pintype "passive"))
      (node (ref "U12") (pin "1") (pinfunction "DIN_1") (pintype "passive"))
    )
    (net (code "29") (name "/DAC1_DOUT") (class "Default")
      (node (ref "U1") (pin "134") (pinfunction "PB4/JNTRST/TIM3_CH1/SPI1_MISO/SPI3_MISO/I2S3ext_SD_134") (pintype "passive"))
      (node (ref "U12") (pin "4") (pinfunction "DOUT_4") (pintype "passive"))
    )
    (net (code "30") (name "/DAC1_SCLK") (class "Default")
      (node (ref "U1") (pin "133") (pinfunction "PB3/JTDO/TRACESWO/TIM2_CH2/SPI1_SCK/SPI3_SCK/I2S3_CK_133") (pintype "passive"))
      (node (ref "U12") (pin "2") (pinfunction "SCLK_2") (pintype "passive"))
    )
    (net (code "31") (name "/DAC2_CS") (class "Default")
      (node (ref "U1") (pin "82") (pinfunction "PD13/FSMC_A18/TIM4_CH2_82") (pintype "passive"))
      (node (ref "U13") (pin "3") (pinfunction "CS#_3") (pintype "passive"))
    )
    (net (code "32") (name "/DAC2_DIN") (class "Default")
      (node (ref "U1") (pin "76") (pinfunction "PB15/SPI2_MOSI/TIM1_CH3N/TIM8_CH3N/TIM12_CH2/OTG_HS_DP/I2S2_SD_76") (pintype "passive"))
      (node (ref "U13") (pin "1") (pinfunction "DIN_1") (pintype "passive"))
    )
    (net (code "33") (name "/DAC2_DOUT") (class "Default")
      (node (ref "U1") (pin "75") (pinfunction "PB14/SPI2_MISO/TIM1_CH2N/TIM8_CH2N/TIM12_CH1/U3_RTS/OTG_HS_DM/I2S2ext_SD_75") (pintype "passive"))
      (node (ref "U13") (pin "4") (pinfunction "DOUT_4") (pintype "passive"))
    )
    (net (code "34") (name "/DAC2_SCLK") (class "Default")
      (node (ref "U1") (pin "74") (pinfunction "PB13/SPI2_SCK/TIM1_CH1N/U3_CTS/CAN2_TX/OTG_HS_ULPI_D6/OTG_HS_VBUS/ETH_MII_TXD1/ETH_RMII_TXD1/I2S2_CK_74") (pintype "passive"))
      (node (ref "U13") (pin "2") (pinfunction "SCLK_2") (pintype "passive"))
    )
    (net (code "35") (name "/DIN3.3V1") (class "Default")
      (node (ref "U1") (pin "65") (pinfunction "PE12/FSMC_D9/TIM1_CH3N_65") (pintype "passive"))
      (node (ref "U14") (pin "17") (pinfunction "B5_17") (pintype "passive"))
    )
    (net (code "36") (name "/DIN3.3V2") (class "Default")
      (node (ref "U1") (pin "66") (pinfunction "PE13/FSMC_D10/TIM1_CH3_66") (pintype "passive"))
      (node (ref "U14") (pin "16") (pinfunction "B6_16") (pintype "passive"))
    )
    (net (code "37") (name "/DIN3.3V3") (class "Default")
      (node (ref "U1") (pin "87") (pinfunction "PG2/FSMC_A12_87") (pintype "passive"))
      (node (ref "U14") (pin "15") (pinfunction "B7_15") (pintype "passive"))
    )
    (net (code "38") (name "/DIN3.3V4") (class "Default")
      (node (ref "U1") (pin "88") (pinfunction "PG3/FSMC_A13_88") (pintype "passive"))
      (node (ref "U14") (pin "14") (pinfunction "B8_14") (pintype "passive"))
    )
    (net (code "39") (name "/DIN3.3V5") (class "Default")
      (node (ref "U1") (pin "59") (pinfunction "PE8/FSMC_D5/TIM1_CH1N_59") (pintype "passive"))
      (node (ref "U14") (pin "21") (pinfunction "B1_21") (pintype "passive"))
    )
    (net (code "40") (name "/DIN3.3V6") (class "Default")
      (node (ref "U1") (pin "60") (pinfunction "PE9/FSMC_D6/TIM1_CH1_60") (pintype "passive"))
      (node (ref "U14") (pin "20") (pinfunction "B2_20") (pintype "passive"))
    )
    (net (code "41") (name "/DIN3.3V7") (class "Default")
      (node (ref "U1") (pin "63") (pinfunction "PE10/FSMC_D7/TIM1_CH2N_63") (pintype "passive"))
      (node (ref "U14") (pin "19") (pinfunction "B3_19") (pintype "passive"))
    )
    (net (code "42") (name "/DIN3.3V8") (class "Default")
      (node (ref "U1") (pin "64") (pinfunction "PE11/FSMC_D8/TIM1_CH2_64") (pintype "passive"))
      (node (ref "U14") (pin "18") (pinfunction "B4_18") (pintype "passive"))
    )
    (net (code "43") (name "/DIN3.3V9") (class "Default")
      (node (ref "U1") (pin "14") (pinfunction "PF4/FSMC_A4/ADC3_IN14_14") (pintype "passive"))
      (node (ref "U15") (pin "21") (pinfunction "B1_21") (pintype "passive"))
    )
    (net (code "44") (name "/DIN3.3V10") (class "Default")
      (node (ref "U1") (pin "15") (pinfunction "PF5/FSMC_A5/ADC3_IN15_15") (pintype "passive"))
      (node (ref "U15") (pin "20") (pinfunction "B2_20") (pintype "passive"))
    )
    (net (code "45") (name "/DIN3.3V11") (class "Default")
      (node (ref "U1") (pin "18") (pinfunction "PF6/TIM10_CH1/FSMC_NIORD/ADC3_IN4_18") (pintype "passive"))
      (node (ref "U15") (pin "19") (pinfunction "B3_19") (pintype "passive"))
    )
    (net (code "46") (name "/DIN3.3V12") (class "Default")
      (node (ref "U1") (pin "54") (pinfunction "PF14/FSMC_A8_54") (pintype "passive"))
      (node (ref "U15") (pin "18") (pinfunction "B4_18") (pintype "passive"))
    )
    (net (code "47") (name "/DIN3.3V13") (class "Default")
      (node (ref "U1") (pin "55") (pinfunction "PF15/FSMC_A9_55") (pintype "passive"))
      (node (ref "U15") (pin "17") (pinfunction "B5_17") (pintype "passive"))
    )
    (net (code "48") (name "/DIN3.3V14") (class "Default")
      (node (ref "U1") (pin "56") (pinfunction "PG0/FSMC_A10_56") (pintype "passive"))
      (node (ref "U15") (pin "16") (pinfunction "B6_16") (pintype "passive"))
    )
    (net (code "49") (name "/DIN3.3V15") (class "Default")
      (node (ref "U1") (pin "57") (pinfunction "PG1/FSMC_A11_57") (pintype "passive"))
      (node (ref "U15") (pin "15") (pinfunction "B7_15") (pintype "passive"))
    )
    (net (code "50") (name "/DIN3.3V16") (class "Default")
      (node (ref "U1") (pin "58") (pinfunction "PE7/FSMC_D4/TIM1_ETR_58") (pintype "passive"))
      (node (ref "U15") (pin "14") (pinfunction "B8_14") (pintype "passive"))
    )
    (net (code "51") (name "/DIN5V1") (class "Default")
      (node (ref "P10") (pin "1") (pinfunction "1_1") (pintype "passive"))
      (node (ref "U14") (pin "7") (pinfunction "A5_7") (pintype "passive"))
    )
    (net (code "52") (name "/DIN5V2") (class "Default")
      (node (ref "P10") (pin "3") (pinfunction "3_3") (pintype "passive"))
      (node (ref "U14") (pin "8") (pinfunction "A6_8") (pintype "passive"))
    )
    (net (code "53") (name "/DIN5V3") (class "Default")
      (node (ref "P10") (pin "5") (pinfunction "5_5") (pintype "passive"))
      (node (ref "U14") (pin "9") (pinfunction "A7_9") (pintype "passive"))
    )
    (net (code "54") (name "/DIN5V4") (class "Default")
      (node (ref "P10") (pin "7") (pinfunction "7_7") (pintype "passive"))
      (node (ref "U14") (pin "10") (pinfunction "A8_10") (pintype "passive"))
    )
    (net (code "55") (name "/DIN5V5") (class "Default")
      (node (ref "P11") (pin "1") (pinfunction "1_1") (pintype "passive"))
      (node (ref "U14") (pin "3") (pinfunction "A1_3") (pintype "passive"))
    )
    (net (code "56") (name "/DIN5V6") (class "Default")
      (node (ref "P11") (pin "3") (pinfunction "3_3") (pintype "passive"))
      (node (ref "U14") (pin "4") (pinfunction "A2_4") (pintype "passive"))
    )
    (net (code "57") (name "/DIN5V7") (class "Default")
      (node (ref "P11") (pin "5") (pinfunction "5_5") (pintype "passive"))
      (node (ref "U14") (pin "5") (pinfunction "A3_5") (pintype "passive"))
    )
    (net (code "58") (name "/DIN5V8") (class "Default")
      (node (ref "P11") (pin "7") (pinfunction "7_7") (pintype "passive"))
      (node (ref "U14") (pin "6") (pinfunction "A4_6") (pintype "passive"))
    )
    (net (code "59") (name "/DIN5V9") (class "Default")
      (node (ref "P12") (pin "1") (pinfunction "1_1") (pintype "passive"))
      (node (ref "U15") (pin "3") (pinfunction "A1_3") (pintype "passive"))
    )
    (net (code "60") (name "/DIN5V10") (class "Default")
      (node (ref "P12") (pin "3") (pinfunction "3_3") (pintype "passive"))
      (node (ref "U15") (pin "4") (pinfunction "A2_4") (pintype "passive"))
    )
    (net (code "61") (name "/DIN5V11") (class "Default")
      (node (ref "P12") (pin "5") (pinfunction "5_5") (pintype "passive"))
      (node (ref "U15") (pin "5") (pinfunction "A3_5") (pintype "passive"))
    )
    (net (code "62") (name "/DIN5V12") (class "Default")
      (node (ref "P12") (pin "7") (pinfunction "7_7") (pintype "passive"))
      (node (ref "U15") (pin "6") (pinfunction "A4_6") (pintype "passive"))
    )
    (net (code "63") (name "/DIN5V13") (class "Default")
      (node (ref "P13") (pin "1") (pinfunction "1_1") (pintype "passive"))
      (node (ref "U15") (pin "7") (pinfunction "A5_7") (pintype "passive"))
    )
    (net (code "64") (name "/DIN5V14") (class "Default")
      (node (ref "P13") (pin "3") (pinfunction "3_3") (pintype "passive"))
      (node (ref "U15") (pin "8") (pinfunction "A6_8") (pintype "passive"))
    )
    (net (code "65") (name "/DIN5V15") (class "Default")
      (node (ref "P13") (pin "5") (pinfunction "5_5") (pintype "passive"))
      (node (ref "U15") (pin "9") (pinfunction "A7_9") (pintype "passive"))
    )
    (net (code "66") (name "/DIN5V16") (class "Default")
      (node (ref "P13") (pin "7") (pinfunction "7_7") (pintype "passive"))
      (node (ref "U15") (pin "10") (pinfunction "A8_10") (pintype "passive"))
    )
    (net (code "67") (name "/DOUT3.3V1") (class "Default")
      (node (ref "U1") (pin "67") (pinfunction "PE14/FSMC_D11/TIM1_CH4_67") (pintype "passive"))
      (node (ref "U11") (pin "21") (pinfunction "B1_21") (pintype "passive"))
    )
    (net (code "68") (name "/DOUT3.3V2") (class "Default")
      (node (ref "U1") (pin "78") (pinfunction "PD9/FSMC_D14/U3_RX_78") (pintype "passive"))
      (node (ref "U11") (pin "18") (pinfunction "B4_18") (pintype "passive"))
    )
    (net (code "69") (name "/DOUT3.3V3") (class "Default")
      (node (ref "U1") (pin "68") (pinfunction "PE15/FSMC_D12/TIM1_BKIN_68") (pintype "passive"))
      (node (ref "U11") (pin "20") (pinfunction "B2_20") (pintype "passive"))
    )
    (net (code "70") (name "/DOUT3.3V4") (class "Default")
      (node (ref "U1") (pin "77") (pinfunction "PD8/FSMC_D13/U3_TX_77") (pintype "passive"))
      (node (ref "U11") (pin "19") (pinfunction "B3_19") (pintype "passive"))
    )
    (net (code "71") (name "/DOUT3.3V5") (class "Default")
      (node (ref "U1") (pin "79") (pinfunction "PD10/FSMC_D15/U3_CK_79") (pintype "passive"))
      (node (ref "U11") (pin "17") (pinfunction "B5_17") (pintype "passive"))
    )
    (net (code "72") (name "/DOUT3.3V6") (class "Default")
      (node (ref "U1") (pin "80") (pinfunction "PD11/FSMC_A16/FSMC_CLE/U3_CTS_80") (pintype "passive"))
      (node (ref "U11") (pin "16") (pinfunction "B6_16") (pintype "passive"))
    )
    (net (code "73") (name "/DOUT5V1") (class "Default")
      (node (ref "P15") (pin "1") (pinfunction "1_1") (pintype "passive"))
      (node (ref "U11") (pin "3") (pinfunction "A1_3") (pintype "passive"))
    )
    (net (code "74") (name "/DOUT5V2") (class "Default")
      (node (ref "P15") (pin "3") (pinfunction "3_3") (pintype "passive"))
      (node (ref "U11") (pin "6") (pinfunction "A4_6") (pintype "passive"))
    )
    (net (code "75") (name "/DOUT5V3") (class "Default")
      (node (ref "P16") (pin "1") (pinfunction "1_1") (pintype "passive"))
      (node (ref "U11") (pin "4") (pinfunction "A2_4") (pintype "passive"))
    )
    (net (code "76") (name "/DOUT5V4") (class "Default")
      (node (ref "P16") (pin "3") (pinfunction "3_3") (pintype "passive"))
      (node (ref "U11") (pin "5") (pinfunction "A3_5") (pintype "passive"))
    )
    (net (code "77") (name "/DOUT5V5") (class "Default")
      (node (ref "P16") (pin "5") (pinfunction "5_5") (pintype "passive"))
      (node (ref "U11") (pin "7") (pinfunction "A5_7") (pintype "passive"))
    )
    (net (code "78") (name "/DOUT5V6") (class "Default")
      (node (ref "P16") (pin "7") (pinfunction "7_7") (pintype "passive"))
      (node (ref "U11") (pin "8") (pinfunction "A6_8") (pintype "passive"))
    )
    (net (code "79") (name "/ESP_RX") (class "Default")
      (node (ref "LED7") (pin "2") (pinfunction "K_2") (pintype "passive"))
      (node (ref "P1") (pin "6") (pinfunction "6_6") (pintype "passive"))
      (node (ref "U3") (pin "15") (pinfunction "RXD0_15") (pintype "passive"))
    )
    (net (code "80") (name "/ESP_TX") (class "Default")
      (node (ref "LED10") (pin "2") (pinfunction "K_2") (pintype "passive"))
      (node (ref "P1") (pin "5") (pinfunction "5_5") (pintype "passive"))
      (node (ref "U3") (pin "16") (pinfunction "TXD0_16") (pintype "passive"))
    )
    (net (code "81") (name "/I2C1_SCL") (class "Default")
      (node (ref "OLED1") (pin "18") (pinfunction "D0_18") (pintype "passive"))
      (node (ref "R50") (pin "2") (pintype "passive"))
      (node (ref "U1") (pin "136") (pinfunction "PB6/TIM4_CH1/U1_TX/CAN2_TX/I2C1_SCL/DCMI_D5_136") (pintype "passive"))
    )
    (net (code "82") (name "/I2C1_SDA") (class "Default")
      (node (ref "OLED1") (pin "19") (pinfunction "D1_19") (pintype "passive"))
      (node (ref "R51") (pin "2") (pintype "passive"))
      (node (ref "R58") (pin "1") (pintype "passive"))
      (node (ref "U1") (pin "137") (pinfunction "PB7/TIM4_CH2/U1_RX/FSMC_NL/I2C1_SDA/DCMI_VSYNC_137") (pintype "passive"))
    )
    (net (code "83") (name "/OLED_RST") (class "Default")
      (node (ref "C51") (pin "1") (pintype "passive"))
      (node (ref "OLED1") (pin "14") (pinfunction "RST_14") (pintype "passive"))
      (node (ref "R48") (pin "1") (pintype "passive"))
    )
    (net (code "84") (name "/PA0") (class "Default")
      (node (ref "P1") (pin "4") (pinfunction "4_4") (pintype "passive"))
      (node (ref "U1") (pin "34") (pinfunction "PA0-WKUP/U2_CTS/U4_TX/ETH_MII_CRS/TIM2_CH1_ETR/TIM5_CH1/TIM8_ETR/ADC123_IN0_34") (pintype "passive"))
    )
    (net (code "85") (name "/PA1") (class "Default")
      (node (ref "P1") (pin "3") (pinfunction "3_3") (pintype "passive"))
      (node (ref "U1") (pin "35") (pinfunction "PA1/U2_RTS/U4_RX/ETH_RMII_REF_CLK/ETH_MII_RX_CLK/TIM2_CH2/TIM5_CH2/ADC123_IN1_35") (pintype "passive"))
    )
    (net (code "86") (name "/PA8") (class "Default")
      (node (ref "U1") (pin "100") (pinfunction "PA8/TIM1_CH1/U1_CK/I2C3_SCL/MCO1/OTG_FS_SOF_100") (pintype "passive"))
    )
    (net (code "87") (name "/PA9") (class "Default")
      (node (ref "LED6") (pin "2") (pinfunction "K_2") (pintype "passive"))
      (node (ref "U1") (pin "101") (pinfunction "PA9/TIM1_CH2/U1_TX/I2C3_SMBA/OTG_FS_VBUS/DCMI_D0_101") (pintype "passive"))
      (node (ref "U7") (pin "3") (pinfunction "RXD_3") (pintype "passive"))
    )
    (net (code "88") (name "/PA10") (class "Default")
      (node (ref "LED5") (pin "2") (pinfunction "K_2") (pintype "passive"))
      (node (ref "U1") (pin "102") (pinfunction "PA10/TIM1_CH3/U1_RX/OTG_FS_ID/DCMI_D1_102") (pintype "passive"))
      (node (ref "U7") (pin "2") (pinfunction "TXD_2") (pintype "passive"))
    )
    (net (code "89") (name "/PA13") (class "Default")
      (node (ref "R17") (pin "1") (pintype "passive"))
      (node (ref "U1") (pin "105") (pinfunction "PA13/JTMS_SWDIO_105") (pintype "passive"))
      (node (ref "U2") (pin "27") (pinfunction "PB14SPI2_MISOUSART3_RTSTIM1_CH2N_27") (pintype "passive"))
    )
    (net (code "90") (name "/PA14") (class "Default")
      (node (ref "U1") (pin "109") (pinfunction "PA14/JTCK_SWCLK_109") (pintype "passive"))
      (node (ref "U2") (pin "15") (pinfunction "PA5SPI1_SCKADC12_IN5_15") (pintype "passive"))
      (node (ref "U2") (pin "26") (pinfunction "PB13SPI2_SCKUSART3_CTSTIM1_CH1N_26") (pintype "passive"))
    )
    (net (code "91") (name "/PA15") (class "Default")
      (node (ref "U1") (pin "110") (pinfunction "PA15/JTDI/SPI1_NSS/SPI3_NSS/TIM2_CH1_ETR/I2S3_WS_110") (pintype "passive"))
    )
    (net (code "92") (name "/PB0") (class "Default")
      (node (ref "U1") (pin "46") (pinfunction "PB0/TIM1_CH2N/TIM3_CH3/TIM8_CH2N/OTG_HS_ULPI_D1/ETH_MII_RXD2/ADC12_IN8_46") (pintype "passive"))
    )
    (net (code "93") (name "/PB1") (class "Default")
      (node (ref "U1") (pin "47") (pinfunction "PB1/TIM1_CH3N/TIM3_CH4/TIM8_CH3N/OTG_HS_INTN/ETH_MII_RXD3/ADC12_IN9_47") (pintype "passive"))
    )
    (net (code "94") (name "/PB8") (class "Default")
      (node (ref "U1") (pin "139") (pinfunction "PB8/TIM4_CH3/TIM10_CH1/CAN1_RX/SDIO_D4/ETH_MII_TXD3/I2C1_SCL/DCMI_D6_139") (pintype "passive"))
    )
    (net (code "95") (name "/PB9") (class "Default")
      (node (ref "U1") (pin "140") (pinfunction "PB9/TIM4_CH4/TIM11_CH1/CAN1_TX/SDIO_D5/SPI2_NSS/I2C1_SDA/DCMI_D7/I2S2_WS_140") (pintype "passive"))
    )
    (net (code "96") (name "/PB10") (class "Default")
      (node (ref "LED12") (pin "2") (pinfunction "K_2") (pintype "passive"))
      (node (ref "U1") (pin "69") (pinfunction "PB10/SPI2_SCK/TIM2_CH3/U3_TX/I2C2_SCL/OTG_HS_ULPI_D3/I2S2_CK_69") (pintype "passive"))
      (node (ref "U4") (pin "10") (pinfunction "T2IN_10") (pintype "passive"))
    )
    (net (code "97") (name "/PB11") (class "Default")
      (node (ref "LED9") (pin "2") (pinfunction "K_2") (pintype "passive"))
      (node (ref "U1") (pin "70") (pinfunction "PB11/TIM2_CH4/U3_RX/I2C2_SDA/HS_ULPI_D4/ETH_MII_TX_EN/ETH_RMII_TX_EN_70") (pintype "passive"))
      (node (ref "U4") (pin "9") (pinfunction "R2OUT_9") (pintype "passive"))
    )
    (net (code "98") (name "/PB12") (class "Default")
      (node (ref "U1") (pin "73") (pinfunction "PB12/SPI2_NSS/TIM1_BKIN/U3_CK/CAN2_RX/I2C2_SMBA/OTG_HS_ULPI_D5/OTG_HS_ID/ETH_MII_TXD0/ETH_RMII_TXD0/I2S2_WS_73") (pintype "passive"))
    )
    (net (code "99") (name "/PC0") (class "Default")
      (node (ref "U1") (pin "26") (pinfunction "PC0/OTG_HS_ULPI_STP/ADC123_IN10_26") (pintype "passive"))
    )
    (net (code "100") (name "/PC1") (class "Default")
      (node (ref "U1") (pin "27") (pinfunction "PC1/ETH_MDC/ADC123_IN11_27") (pintype "passive"))
    )
    (net (code "101") (name "/PC2") (class "Default")
      (node (ref "U1") (pin "28") (pinfunction "PC2/SPI2_MISO/OTG_HS_ULPI_DIR/ETH_MII_TXD2/I2S2ext_SD/ADC123_IN12_28") (pintype "passive"))
    )
    (net (code "102") (name "/PC6") (class "Default")
      (node (ref "LED13") (pin "2") (pinfunction "K_2") (pintype "passive"))
      (node (ref "U1") (pin "96") (pinfunction "PC6/TIM3_CH1/TIM8_CH1/U6_TX/SDIO_D6/DCMI_D0/I2S2_MCK_96") (pintype "passive"))
      (node (ref "U5") (pin "11") (pinfunction "T1IN_11") (pintype "passive"))
    )
    (net (code "103") (name "/PC7") (class "Default")
      (node (ref "LED14") (pin "2") (pinfunction "K_2") (pintype "passive"))
      (node (ref "U1") (pin "97") (pinfunction "PC7/TIM3_CH2/TIM8_CH2/U6_RX/SDIO_D7/DCMI_D1/I2S3_MCK_97") (pintype "passive"))
      (node (ref "U5") (pin "12") (pinfunction "R1OUT_12") (pintype "passive"))
    )
    (net (code "104") (name "/PC8") (class "Default")
      (node (ref "R55") (pin "1") (pintype "passive"))
      (node (ref "SD_CARD1") (pin "7") (pinfunction "DATA0_7") (pintype "passive"))
      (node (ref "U1") (pin "98") (pinfunction "PC8/TIM3_CH3/TIM8_CH3/U6_CK/SDIO_D0/DCMI_D2_98") (pintype "passive"))
    )
    (net (code "105") (name "/PC9") (class "Default")
      (node (ref "R56") (pin "1") (pintype "passive"))
      (node (ref "SD_CARD1") (pin "8") (pinfunction "DATA1_8") (pintype "passive"))
      (node (ref "U1") (pin "99") (pinfunction "PC9/TIM3_CH4/TIM8_CH4/I2C3_SDA/SDIO_D1/DCMI_D3/MCO2/I2S_CKIN_99") (pintype "passive"))
    )
    (net (code "106") (name "/PC10") (class "Default")
      (node (ref "R52") (pin "1") (pintype "passive"))
      (node (ref "SD_CARD1") (pin "9") (pinfunction "DATA2_9") (pintype "passive"))
      (node (ref "U1") (pin "111") (pinfunction "PC10/SPI3_SCK/U3_TX/U4_TX/SDIO_D2/DCMI_D8/I2S3_CK_111") (pintype "passive"))
    )
    (net (code "107") (name "/PC11") (class "Default")
      (node (ref "R53") (pin "1") (pintype "passive"))
      (node (ref "SD_CARD1") (pin "1") (pinfunction "CD/DATA3_1") (pintype "passive"))
      (node (ref "U1") (pin "112") (pinfunction "PC11/SPI3_MISO/U3_RX/U4_RX/SDIO_D3/DCMI_D4/I2S3ext_SD_112") (pintype "passive"))
    )
    (net (code "108") (name "/PC12") (class "Default")
      (node (ref "SD_CARD1") (pin "5") (pinfunction "CLK_5") (pintype "passive"))
      (node (ref "U1") (pin "113") (pinfunction "PC12/SPI3_MOSI/U3_CK/U5_TX/SDIO_CK/DCMI_D9/I2S3_SD_113") (pintype "passive"))
    )
    (net (code "109") (name "/PC13") (class "Default")
      (node (ref "U1") (pin "7") (pinfunction "PC13/RTC_AF1_7") (pintype "passive"))
    )
    (net (code "110") (name "/PC14") (class "Default")
      (node (ref "C4") (pin "2") (pintype "passive"))
      (node (ref "U1") (pin "8") (pinfunction "PC14-OSC32_IN_8") (pintype "passive"))
      (node (ref "Y1") (pin "1") (pinfunction "OSC1_1") (pintype "passive"))
    )
    (net (code "111") (name "/PC15") (class "Default")
      (node (ref "C3") (pin "1") (pintype "passive"))
      (node (ref "U1") (pin "9") (pinfunction "PC15-OSC32_OUT_9") (pintype "passive"))
      (node (ref "Y1") (pin "2") (pinfunction "OSC2_2") (pintype "passive"))
    )
    (net (code "112") (name "/PD0") (class "Default")
      (node (ref "U1") (pin "114") (pinfunction "PD0/FSMC_D2/CAN1_RX_114") (pintype "passive"))
    )
    (net (code "113") (name "/PD1") (class "Default")
      (node (ref "U1") (pin "115") (pinfunction "PD1/FSMC_D3/CAN1_TX_115") (pintype "passive"))
    )
    (net (code "114") (name "/PD2") (class "Default")
      (node (ref "R54") (pin "1") (pintype "passive"))
      (node (ref "SD_CARD1") (pin "2") (pinfunction "CMD_2") (pintype "passive"))
      (node (ref "U1") (pin "116") (pinfunction "PD2/TIM3_ETR/U5_RX/SDIO_CMD/DCMI_D11_116") (pintype "passive"))
    )
    (net (code "115") (name "/PD3") (class "Default")
      (node (ref "U1") (pin "117") (pinfunction "PD3/FSMC_CLK/U2_CTS_117") (pintype "passive"))
    )
    (net (code "116") (name "/PD4") (class "Default")
      (node (ref "U1") (pin "118") (pinfunction "PD4/FSMC_NOE/U2_RTS_118") (pintype "passive"))
    )
    (net (code "117") (name "/PD5") (class "Default")
      (node (ref "LED11") (pin "2") (pinfunction "K_2") (pintype "passive"))
      (node (ref "U1") (pin "119") (pinfunction "PD5/FSMC_NWE/U2_TX_119") (pintype "passive"))
      (node (ref "U4") (pin "11") (pinfunction "T1IN_11") (pintype "passive"))
    )
    (net (code "118") (name "/PD6") (class "Default")
      (node (ref "LED8") (pin "2") (pinfunction "K_2") (pintype "passive"))
      (node (ref "U1") (pin "122") (pinfunction "PD6/FSMC_NWAIT/U2_RX_122") (pintype "passive"))
      (node (ref "U4") (pin "12") (pinfunction "R1OUT_12") (pintype "passive"))
    )
    (net (code "119") (name "/PD7") (class "Default")
      (node (ref "U1") (pin "123") (pinfunction "PD7/FSMC_NE1/FSMC_NCE2/U2_CK_123") (pintype "passive"))
    )
    (net (code "120") (name "/PD14") (class "Default")
      (node (ref "U1") (pin "85") (pinfunction "PD14/FSMC_D0/TIM4_CH3_85") (pintype "passive"))
    )
    (net (code "121") (name "/PD15") (class "Default")
      (node (ref "U1") (pin "86") (pinfunction "PD15/FSMC_D1/TIM4_CH4_86") (pintype "passive"))
    )
    (net (code "122") (name "/PE0") (class "Default")
      (node (ref "U1") (pin "141") (pinfunction "PE0/TIM4_ETR/FSMC_NBL0/DCMI_D2_141") (pintype "passive"))
    )
    (net (code "123") (name "/PE1") (class "Default")
      (node (ref "U1") (pin "142") (pinfunction "PE1/FSMC_NBL1/DCMI_D3_142") (pintype "passive"))
    )
    (net (code "124") (name "/PE2") (class "Default")
      (node (ref "U1") (pin "1") (pinfunction "PE2/TRACECLK/FSMC_A23/ETH_MII_TXD3_1") (pintype "passive"))
    )
    (net (code "125") (name "/PE3") (class "Default")
      (node (ref "U1") (pin "2") (pinfunction "PE3/TRACED0/FSMC_A19_2") (pintype "passive"))
    )
    (net (code "126") (name "/PE4") (class "Default")
      (node (ref "U1") (pin "3") (pinfunction "PE4/TRACED1/FSMC_A20/DCMI_D4_3") (pintype "passive"))
    )
    (net (code "127") (name "/PE5") (class "Default")
      (node (ref "U1") (pin "4") (pinfunction "PE5/TRACED2/FSMC_A21/TIM9_CH1/DCMI_D6_4") (pintype "passive"))
    )
    (net (code "128") (name "/PE6") (class "Default")
      (node (ref "U1") (pin "5") (pinfunction "PE6/TRACED3/FSMC_A22/TIM9_CH2/DCMI_D7_5") (pintype "passive"))
    )
    (net (code "129") (name "/PF0") (class "Default")
      (node (ref "U1") (pin "10") (pinfunction "PF0/FSMC_A0/I2C2_SDA_10") (pintype "passive"))
    )
    (net (code "130") (name "/PF1") (class "Default")
      (node (ref "U1") (pin "11") (pinfunction "PF1/FSMC_A1/I2C2_SCL_11") (pintype "passive"))
    )
    (net (code "131") (name "/PF2") (class "Default")
      (node (ref "U1") (pin "12") (pinfunction "PF2/FSMC_A2/I2C2_SMBA_12") (pintype "passive"))
    )
    (net (code "132") (name "/PF3") (class "Default")
      (node (ref "U1") (pin "13") (pinfunction "PF3/FSMC_A3/ADC3_IN9_13") (pintype "passive"))
    )
    (net (code "133") (name "/PF7") (class "Default")
      (node (ref "U1") (pin "19") (pinfunction "PF7/TIM11_CH1/FSMC_NREG/ADC3_IN5_19") (pintype "passive"))
    )
    (net (code "134") (name "/PF8") (class "Default")
      (node (ref "U1") (pin "20") (pinfunction "PF8/TIM13_CH1/FSMC_NIOWR/ADC3_IN6_20") (pintype "passive"))
    )
    (net (code "135") (name "/PF9") (class "Default")
      (node (ref "U1") (pin "21") (pinfunction "PF9/TIM14_CH1/FSMC_CD/ADC3_IN7_21") (pintype "passive"))
    )
    (net (code "136") (name "/PF10") (class "Default")
      (node (ref "U1") (pin "22") (pinfunction "PF10/FSMC_INTR/ADC3_IN8_22") (pintype "passive"))
    )
    (net (code "137") (name "/PF11") (class "Default")
      (node (ref "U1") (pin "49") (pinfunction "PF11/DCMI_D12_49") (pintype "passive"))
    )
    (net (code "138") (name "/PF12") (class "Default")
      (node (ref "U1") (pin "50") (pinfunction "PF12/FSMC_A6_50") (pintype "passive"))
    )
    (net (code "139") (name "/PF13") (class "Default")
      (node (ref "U1") (pin "53") (pinfunction "PF13/FSMC_A7_53") (pintype "passive"))
    )
    (net (code "140") (name "/PG4") (class "Default")
      (node (ref "U1") (pin "89") (pinfunction "PG4/FSMC_A14_89") (pintype "passive"))
    )
    (net (code "141") (name "/PG5") (class "Default")
      (node (ref "U1") (pin "90") (pinfunction "PG5/FSMC_A15_90") (pintype "passive"))
    )
    (net (code "142") (name "/PG6") (class "Default")
      (node (ref "U1") (pin "91") (pinfunction "PG6/FSMC_INT2_91") (pintype "passive"))
    )
    (net (code "143") (name "/PG7") (class "Default")
      (node (ref "U1") (pin "92") (pinfunction "PG7/FSMC_INT3/U6_CK_92") (pintype "passive"))
    )
    (net (code "144") (name "/PG8") (class "Default")
      (node (ref "U1") (pin "93") (pinfunction "PG8/U6_RTS/ETH_PPS_OUT_93") (pintype "passive"))
    )
    (net (code "145") (name "/PG9") (class "Default")
      (node (ref "U1") (pin "124") (pinfunction "PG9/FSMC_NE2/FSMC_NCE3/U6_RX_124") (pintype "passive"))
    )
    (net (code "146") (name "/PG10") (class "Default")
      (node (ref "U1") (pin "125") (pinfunction "PG10/FSMC_NCE4_1/FSMC_NE3_125") (pintype "passive"))
    )
    (net (code "147") (name "/PG11") (class "Default")
      (node (ref "U1") (pin "126") (pinfunction "PG11/FSMC_NCE4_2/ETH_MII_TX_EN/ETH_RMII_TX_EN_126") (pintype "passive"))
    )
    (net (code "148") (name "/PG12") (class "Default")
      (node (ref "U1") (pin "127") (pinfunction "PG12/FSMC_NE4/U6_RTS_127") (pintype "passive"))
    )
    (net (code "149") (name "/PG13") (class "Default")
      (node (ref "U1") (pin "128") (pinfunction "PG13/FSMC_A24/U6_CTS/ETH_MII_TXD0/ETH_RMII_TXD0_128") (pintype "passive"))
    )
    (net (code "150") (name "/PG14") (class "Default")
      (node (ref "U1") (pin "129") (pinfunction "PG14/FSMC_A25/U6_TX/ETH_MII_TXD1/ETH_RMII_TXD1_129") (pintype "passive"))
    )
    (net (code "151") (name "/PG15") (class "Default")
      (node (ref "U1") (pin "132") (pinfunction "PG15/U6_CTS/DCMI_D13_132") (pintype "passive"))
    )
    (net (code "152") (name "/RS232_1_RX") (class "Default")
      (node (ref "P5") (pin "2") (pinfunction "2_2") (pintype "passive"))
      (node (ref "U4") (pin "14") (pinfunction "T1OUT_14") (pintype "passive"))
    )
    (net (code "153") (name "/RS232_1_TX") (class "Default")
      (node (ref "P5") (pin "3") (pinfunction "3_3") (pintype "passive"))
      (node (ref "U4") (pin "13") (pinfunction "R1IN_13") (pintype "passive"))
    )
    (net (code "154") (name "/RS232_2_RX") (class "Default")
      (node (ref "P6") (pin "2") (pinfunction "2_2") (pintype "passive"))
      (node (ref "U4") (pin "7") (pinfunction "T2OUT_7") (pintype "passive"))
    )
    (net (code "155") (name "/RS232_2_TX") (class "Default")
      (node (ref "P6") (pin "3") (pinfunction "3_3") (pintype "passive"))
      (node (ref "U4") (pin "8") (pinfunction "R2IN_8") (pintype "passive"))
    )
    (net (code "156") (name "/RS232_3_RX") (class "Default")
      (node (ref "P7") (pin "2") (pinfunction "2_2") (pintype "passive"))
      (node (ref "U5") (pin "14") (pinfunction "T1OUT_14") (pintype "passive"))
    )
    (net (code "157") (name "/RS232_3_TX") (class "Default")
      (node (ref "P7") (pin "3") (pinfunction "3_3") (pintype "passive"))
      (node (ref "U5") (pin "13") (pinfunction "R1IN_13") (pintype "passive"))
    )
    (net (code "158") (name "/RST") (class "Default")
      (node (ref "C34") (pin "1") (pintype "passive"))
      (node (ref "C7") (pin "1") (pintype "passive"))
      (node (ref "K1") (pin "1") (pinfunction "1_1") (pintype "passive"))
      (node (ref "R14") (pin "2") (pintype "passive"))
      (node (ref "U1") (pin "25") (pinfunction "NRST_25") (pintype "passive"))
      (node (ref "U2") (pin "18") (pinfunction "PB0ADC12_IN8TIM3_CH3_18") (pintype "passive"))
    )
    (net (code "159") (name "/STLINK_RX") (class "Default")
      (node (ref "P1") (pin "2") (pinfunction "2_2") (pintype "passive"))
      (node (ref "U2") (pin "13") (pinfunction "PA3USART2_RXADC12_IN3TIM2_CH4_13") (pintype "passive"))
    )
    (net (code "160") (name "/STLINK_TX") (class "Default")
      (node (ref "P1") (pin "1") (pinfunction "1_1") (pintype "passive"))
      (node (ref "U2") (pin "12") (pinfunction "PA2USART2_TXADC12_IN2TIM2_CH3_12") (pintype "passive"))
    )
    (net (code "161") (name "/STp_AIN") (class "Default")
      (node (ref "R1") (pin "1") (pintype "passive"))
      (node (ref "R2") (pin "2") (pintype "passive"))
      (node (ref "U2") (pin "10") (pinfunction "PA0_WKUPUSART2_CTSADC12_IN0TIM2_CH1_ETR_10") (pintype "passive"))
    )
    (net (code "162") (name "/STp_LED") (class "Default")
      (node (ref "R20") (pin "2") (pintype "passive"))
      (node (ref "U2") (pin "30") (pinfunction "PA9USART1_TXTIM1_CH2_30") (pintype "passive"))
    )
    (net (code "163") (name "/STp_NRST") (class "Default")
      (node (ref "C5") (pin "2") (pintype "passive"))
      (node (ref "P3") (pin "4") (pinfunction "4_4") (pintype "passive"))
      (node (ref "R4") (pin "1") (pintype "passive"))
      (node (ref "U2") (pin "7") (pinfunction "NRST_7") (pintype "passive"))
    )
    (net (code "164") (name "/STp_SWCLK") (class "Default")
      (node (ref "P3") (pin "2") (pinfunction "2_2") (pintype "passive"))
      (node (ref "U2") (pin "37") (pinfunction "PA14JTCKSWCLK_37") (pintype "passive"))
    )
    (net (code "165") (name "/STp_SWDIO") (class "Default")
      (node (ref "P3") (pin "3") (pinfunction "3_3") (pintype "passive"))
      (node (ref "U2") (pin "34") (pinfunction "PA13JTMSSWDIO_34") (pintype "passive"))
    )
    (net (code "166") (name "/STp_USBDN") (class "Default")
      (node (ref "R12") (pin "1") (pintype "passive"))
      (node (ref "USB1") (pin "A7") (pinfunction "D-_A7") (pintype "passive"))
      (node (ref "USB1") (pin "B7") (pinfunction "D-_B7") (pintype "passive"))
    )
    (net (code "167") (name "/STp_USBDP") (class "Default")
      (node (ref "R13") (pin "1") (pintype "passive"))
      (node (ref "R9") (pin "1") (pintype "passive"))
      (node (ref "USB1") (pin "A6") (pinfunction "D+_A6") (pintype "passive"))
      (node (ref "USB1") (pin "B6") (pinfunction "D+_B6") (pintype "passive"))
    )
    (net (code "168") (name "/STp_USBN") (class "Default")
      (node (ref "R12") (pin "2") (pintype "passive"))
      (node (ref "U2") (pin "32") (pinfunction "PA11USART1_CTSCAN_RXTIM1_CH4USBDM_32") (pintype "passive"))
    )
    (net (code "169") (name "/STp_USBP") (class "Default")
      (node (ref "R13") (pin "2") (pintype "passive"))
      (node (ref "U2") (pin "33") (pinfunction "PA12USART1_RTSCAN_TXTIM1_ETRUSBDP_33") (pintype "passive"))
    )
    (net (code "170") (name "/STp_USBRENU") (class "Default")
      (node (ref "R3") (pin "2") (pintype "passive"))
      (node (ref "U2") (pin "38") (pinfunction "PA15JTDI_38") (pintype "passive"))
    )
    (net (code "172") (name "/VBAT") (class "Default")
      (node (ref "C6") (pin "1") (pintype "passive"))
      (node (ref "D1") (pin "2") (pintype "passive"))
      (node (ref "D2") (pin "2") (pintype "passive"))
      (node (ref "U1") (pin "6") (pinfunction "VBAT_6") (pintype "passive"))
    )
    (net (code "175") (name "3.3V") (class "Default")
      (node (ref "BEEP1") (pin "1") (pinfunction "P_1") (pintype "passive"))
      (node (ref "C35") (pin "2") (pintype "passive"))
      (node (ref "C36") (pin "2") (pintype "passive"))
      (node (ref "C37") (pin "2") (pintype "passive"))
      (node (ref "C38") (pin "2") (pintype "passive"))
      (node (ref "C40") (pin "2") (pintype "passive"))
      (node (ref "C42") (pin "2") (pintype "passive"))
      (node (ref "C56") (pin "2") (pintype "passive"))
      (node (ref "C61") (pin "1") (pinfunction "VCC_1") (pintype "passive"))
      (node (ref "LED3") (pin "1") (pinfunction "A_1") (pintype "passive"))
      (node (ref "OLED1") (pin "6") (pinfunction "VBAT_6") (pintype "passive"))
      (node (ref "OLED1") (pin "9") (pinfunction "VDD_9") (pintype "passive"))
      (node (ref "R40") (pin "2") (pintype "passive"))
      (node (ref "R41") (pin "2") (pintype "passive"))
      (node (ref "R43") (pin "2") (pintype "passive"))
      (node (ref "R44") (pin "2") (pintype "passive"))
      (node (ref "R45") (pin "2") (pintype "passive"))
      (node (ref "R46") (pin "2") (pintype "passive"))
      (node (ref "R48") (pin "2") (pintype "passive"))
      (node (ref "R49") (pin "1") (pintype "passive"))
      (node (ref "R50") (pin "1") (pintype "passive"))
      (node (ref "R51") (pin "1") (pintype "passive"))
      (node (ref "R52") (pin "2") (pintype "passive"))
      (node (ref "R53") (pin "2") (pintype "passive"))
      (node (ref "R54") (pin "2") (pintype "passive"))
      (node (ref "R55") (pin "2") (pintype "passive"))
      (node (ref "R56") (pin "2") (pintype "passive"))
      (node (ref "R61") (pin "1") (pintype "passive"))
      (node (ref "R62") (pin "1") (pintype "passive"))
      (node (ref "R63") (pin "1") (pintype "passive"))
      (node (ref "SD_CARD1") (pin "4") (pinfunction "VDD_4") (pintype "passive"))
      (node (ref "U11") (pin "23") (pinfunction "VCCB_23") (pintype "passive"))
      (node (ref "U11") (pin "24") (pinfunction "VCCB_24") (pintype "passive"))
      (node (ref "U14") (pin "23") (pinfunction "VCCB_23") (pintype "passive"))
      (node (ref "U14") (pin "24") (pinfunction "VCCB_24") (pintype "passive"))
      (node (ref "U15") (pin "23") (pinfunction "VCCB_23") (pintype "passive"))
      (node (ref "U15") (pin "24") (pinfunction "VCCB_24") (pintype "passive"))
      (node (ref "U4") (pin "16") (pinfunction "VCC_16") (pintype "passive"))
      (node (ref "U5") (pin "16") (pinfunction "VCC_16") (pintype "passive"))
      (node (ref "U8") (pin "2") (pinfunction "OUT_2") (pintype "passive"))
      (node (ref "U8") (pin "4") (pinfunction "OUT_4") (pintype "passive"))
    )
    (net (code "176") (name "3.3V2") (class "Default")
      (node (ref "C57") (pin "2") (pintype "passive"))
      (node (ref "C62") (pin "1") (pinfunction "VCC_1") (pintype "passive"))
      (node (ref "R60") (pin "1") (pintype "passive"))
      (node (ref "U9") (pin "2") (pinfunction "OUT_2") (pintype "passive"))
      (node (ref "U9") (pin "4") (pinfunction "OUT_4") (pintype "passive"))
    )
    (net (code "177") (name "5V") (class "Default")
      (node (ref "C25") (pin "2") (pintype "passive"))
      (node (ref "C26") (pin "2") (pintype "passive"))
      (node (ref "C28") (pin "2") (pintype "passive"))
      (node (ref "C29") (pin "2") (pintype "passive"))
      (node (ref "C31") (pin "2") (pintype "passive"))
      (node (ref "C32") (pin "2") (pintype "passive"))
      (node (ref "C39") (pin "2") (pintype "passive"))
      (node (ref "C43") (pin "2") (pintype "passive"))
      (node (ref "C44") (pin "1") (pinfunction "VCC_1") (pintype "passive"))
      (node (ref "C49") (pin "2") (pintype "passive"))
      (node (ref "C50") (pin "2") (pintype "passive"))
      (node (ref "F1") (pin "2") (pinfunction "2_2") (pintype "passive"))
      (node (ref "L1") (pin "1") (pintype "passive"))
      (node (ref "LED4") (pin "1") (pinfunction "A_1") (pintype "passive"))
      (node (ref "R36") (pin "2") (pintype "passive"))
      (node (ref "R37") (pin "2") (pintype "passive"))
      (node (ref "R38") (pin "2") (pintype "passive"))
      (node (ref "R5") (pin "1") (pintype "passive"))
      (node (ref "R76") (pin "2") (pintype "passive"))
      (node (ref "R78") (pin "2") (pintype "passive"))
      (node (ref "R80") (pin "1") (pintype "passive"))
      (node (ref "R81") (pin "1") (pintype "passive"))
      (node (ref "U10") (pin "3") (pinfunction "VCC_3") (pintype "power_in"))
      (node (ref "U11") (pin "1") (pinfunction "VCCA_1") (pintype "passive"))
      (node (ref "U12") (pin "8") (pinfunction "VDD_8") (pintype "passive"))
      (node (ref "U13") (pin "8") (pinfunction "VDD_8") (pintype "passive"))
      (node (ref "U14") (pin "1") (pinfunction "VCCA_1") (pintype "passive"))
      (node (ref "U15") (pin "1") (pinfunction "VCCA_1") (pintype "passive"))
      (node (ref "U7") (pin "16") (pinfunction "VCC_16") (pintype "passive"))
      (node (ref "U8") (pin "3") (pinfunction "IN_3") (pintype "passive"))
      (node (ref "U9") (pin "3") (pinfunction "IN_3") (pintype "passive"))
    )
    (net (code "178") (name "ESP_3.3V") (class "Default")
      (node (ref "C54") (pin "2") (pintype "passive"))
      (node (ref "R25") (pin "2") (pintype "passive"))
      (node (ref "R26") (pin "2") (pintype "passive"))
      (node (ref "R33") (pin "2") (pintype "passive"))
      (node (ref "R34") (pin "2") (pintype "passive"))
      (node (ref "R39") (pin "2") (pintype "passive"))
      (node (ref "R42") (pin "2") (pintype "passive"))
      (node (ref "R60") (pin "2") (pintype "passive"))
      (node (ref "U3") (pin "8") (pinfunction "VCC_8") (pintype "passive"))
    )
    (net (code "179") (name "GND") (class "Default")
      (node (ref "BAT1") (pin "2") (pinfunction "GND_2") (pintype "passive"))
      (node (ref "C1") (pin "1") (pintype "passive"))
      (node (ref "C10") (pin "1") (pintype "passive"))
      (node (ref "C11") (pin "1") (pintype "passive"))
      (node (ref "C12") (pin "2") (pintype "passive"))
      (node (ref "C13") (pin "1") (pintype "passive"))
      (node (ref "C14") (pin "1") (pintype "passive"))
      (node (ref "C15") (pin "1") (pintype "passive"))
      (node (ref "C16") (pin "1") (pintype "passive"))
      (node (ref "C17") (pin "1") (pintype "passive"))
      (node (ref "C18") (pin "1") (pintype "passive"))
      (node (ref "C19") (pin "1") (pintype "passive"))
      (node (ref "C2") (pin "2") (pintype "passive"))
      (node (ref "C20") (pin "1") (pintype "passive"))
      (node (ref "C25") (pin "1") (pintype "passive"))
      (node (ref "C26") (pin "1") (pintype "passive"))
      (node (ref "C27") (pin "1") (pintype "passive"))
      (node (ref "C28") (pin "1") (pintype "passive"))
      (node (ref "C29") (pin "1") (pintype "passive"))
      (node (ref "C3") (pin "2") (pintype "passive"))
      (node (ref "C30") (pin "1") (pintype "passive"))
      (node (ref "C31") (pin "1") (pintype "passive"))
      (node (ref "C32") (pin "1") (pintype "passive"))
      (node (ref "C35") (pin "1") (pintype "passive"))
      (node (ref "C36") (pin "1") (pintype "passive"))
      (node (ref "C37") (pin "1") (pintype "passive"))
      (node (ref "C38") (pin "1") (pintype "passive"))
      (node (ref "C4") (pin "1") (pintype "passive"))
      (node (ref "C40") (pin "1") (pintype "passive"))
      (node (ref "C41") (pin "2") (pintype "passive"))
      (node (ref "C42") (pin "1") (pintype "passive"))
      (node (ref "C43") (pin "1") (pintype "passive"))
      (node (ref "C44") (pin "2") (pinfunction "GND_2") (pintype "passive"))
      (node (ref "C45") (pin "1") (pintype "passive"))
      (node (ref "C46") (pin "1") (pintype "passive"))
      (node (ref "C47") (pin "1") (pintype "passive"))
      (node (ref "C48") (pin "1") (pintype "passive"))
      (node (ref "C49") (pin "1") (pintype "passive"))
      (node (ref "C5") (pin "1") (pintype "passive"))
      (node (ref "C50") (pin "1") (pintype "passive"))
      (node (ref "C51") (pin "2") (pintype "passive"))
      (node (ref "C52") (pin "1") (pintype "passive"))
      (node (ref "C53") (pin "1") (pintype "passive"))
      (node (ref "C54") (pin "1") (pintype "passive"))
      (node (ref "C55") (pin "1") (pintype "passive"))
      (node (ref "C56") (pin "1") (pintype "passive"))
      (node (ref "C57") (pin "1") (pintype "passive"))
      (node (ref "C58") (pin "1") (pintype "passive"))
      (node (ref "C6") (pin "2") (pintype "passive"))
      (node (ref "C61") (pin "2") (pinfunction "GND_2") (pintype "passive"))
      (node (ref "C62") (pin "2") (pinfunction "GND_2") (pintype "passive"))
      (node (ref "C7") (pin "2") (pintype "passive"))
      (node (ref "C8") (pin "1") (pintype "passive"))
      (node (ref "C9") (pin "1") (pintype "passive"))
      (node (ref "D4") (pin "1") (pintype "passive"))
      (node (ref "K1") (pin "2") (pinfunction "2_2") (pintype "passive"))
      (node (ref "OLED1") (pin "1") (pinfunction "NC(VSS)_1") (pintype "passive"))
      (node (ref "OLED1") (pin "10") (pinfunction "BS0_10") (pintype "passive"))
      (node (ref "OLED1") (pin "12") (pinfunction "BS2_12") (pintype "passive"))
      (node (ref "OLED1") (pin "13") (pinfunction "CS_13") (pintype "passive"))
      (node (ref "OLED1") (pin "15") (pinfunction "D/C_15") (pintype "passive"))
      (node (ref "OLED1") (pin "16") (pinfunction "R/W_16") (pintype "passive"))
      (node (ref "OLED1") (pin "17") (pinfunction "E/RD_17") (pintype "passive"))
      (node (ref "OLED1") (pin "21") (pinfunction "D3_21") (pintype "passive"))
      (node (ref "OLED1") (pin "22") (pinfunction "D4_22") (pintype "passive"))
      (node (ref "OLED1") (pin "23") (pinfunction "D5_23") (pintype "passive"))
      (node (ref "OLED1") (pin "24") (pinfunction "D6_24") (pintype "passive"))
      (node (ref "OLED1") (pin "25") (pinfunction "D7_25") (pintype "passive"))
      (node (ref "OLED1") (pin "29") (pinfunction "VLSS_29") (pintype "passive"))
      (node (ref "OLED1") (pin "30") (pinfunction "NC(VSS)_30") (pintype "passive"))
      (node (ref "OLED1") (pin "8") (pinfunction "VSS_8") (pintype "passive"))
      (node (ref "P10") (pin "2") (pinfunction "2_2") (pintype "passive"))
      (node (ref "P10") (pin "4") (pinfunction "4_4") (pintype "passive"))
      (node (ref "P10") (pin "6") (pinfunction "6_6") (pintype "passive"))
      (node (ref "P10") (pin "8") (pinfunction "8_8") (pintype "passive"))
      (node (ref "P11") (pin "2") (pinfunction "2_2") (pintype "passive"))
      (node (ref "P11") (pin "4") (pinfunction "4_4") (pintype "passive"))
      (node (ref "P11") (pin "6") (pinfunction "6_6") (pintype "passive"))
      (node (ref "P11") (pin "8") (pinfunction "8_8") (pintype "passive"))
      (node (ref "P12") (pin "2") (pinfunction "2_2") (pintype "passive"))
      (node (ref "P12") (pin "4") (pinfunction "4_4") (pintype "passive"))
      (node (ref "P12") (pin "6") (pinfunction "6_6") (pintype "passive"))
      (node (ref "P12") (pin "8") (pinfunction "8_8") (pintype "passive"))
      (node (ref "P13") (pin "2") (pinfunction "2_2") (pintype "passive"))
      (node (ref "P13") (pin "4") (pinfunction "4_4") (pintype "passive"))
      (node (ref "P13") (pin "6") (pinfunction "6_6") (pintype "passive"))
      (node (ref "P13") (pin "8") (pinfunction "8_8") (pintype "passive"))
      (node (ref "P14") (pin "2") (pinfunction "2_2") (pintype "passive"))
      (node (ref "P14") (pin "4") (pinfunction "4_4") (pintype "passive"))
      (node (ref "P14") (pin "6") (pinfunction "6_6") (pintype "passive"))
      (node (ref "P14") (pin "8") (pinfunction "8_8") (pintype "passive"))
      (node (ref "P15") (pin "2") (pinfunction "2_2") (pintype "passive"))
      (node (ref "P15") (pin "4") (pinfunction "4_4") (pintype "passive"))
      (node (ref "P15") (pin "6") (pinfunction "6_6") (pintype "passive"))
      (node (ref "P15") (pin "8") (pinfunction "8_8") (pintype "passive"))
      (node (ref "P16") (pin "2") (pinfunction "2_2") (pintype "passive"))
      (node (ref "P16") (pin "4") (pinfunction "4_4") (pintype "passive"))
      (node (ref "P16") (pin "6") (pinfunction "6_6") (pintype "passive"))
      (node (ref "P16") (pin "8") (pinfunction "8_8") (pintype "passive"))
      (node (ref "P2") (pin "5") (pinfunction "5_5") (pintype "passive"))
      (node (ref "P2") (pin "6") (pinfunction "6_6") (pintype "passive"))
      (node (ref "P3") (pin "5") (pinfunction "5_5") (pintype "passive"))
      (node (ref "P4") (pin "1") (pinfunction "1_1") (pintype "passive"))
      (node (ref "P5") (pin "5") (pinfunction "5_5") (pintype "passive"))
      (node (ref "P6") (pin "5") (pinfunction "5_5") (pintype "passive"))
      (node (ref "P7") (pin "5") (pinfunction "5_5") (pintype "passive"))
      (node (ref "P9") (pin "2") (pinfunction "2_2") (pintype "passive"))
      (node (ref "P9") (pin "4") (pinfunction "4_4") (pintype "passive"))
      (node (ref "P9") (pin "6") (pinfunction "6_6") (pintype "passive"))
      (node (ref "P9") (pin "8") (pinfunction "8_8") (pintype "passive"))
      (node (ref "R10") (pin "1") (pintype "passive"))
      (node (ref "R11") (pin "2") (pintype "passive"))
      (node (ref "R16") (pin "2") (pintype "passive"))
      (node (ref "R2") (pin "1") (pintype "passive"))
      (node (ref "R21") (pin "2") (pintype "passive"))
      (node (ref "R24") (pin "1") (pintype "passive"))
      (node (ref "R28") (pin "2") (pintype "passive"))
      (node (ref "R29") (pin "2") (pintype "passive"))
      (node (ref "R30") (pin "2") (pintype "passive"))
      (node (ref "R31") (pin "2") (pintype "passive"))
      (node (ref "R35") (pin "2") (pintype "passive"))
      (node (ref "R47") (pin "1") (pintype "passive"))
      (node (ref "R57") (pin "1") (pintype "passive"))
      (node (ref "R6") (pin "2") (pintype "passive"))
      (node (ref "R64") (pin "1") (pintype "passive"))
      (node (ref "R66") (pin "1") (pintype "passive"))
      (node (ref "R67") (pin "1") (pintype "passive"))
      (node (ref "R69") (pin "1") (pintype "passive"))
      (node (ref "R7") (pin "1") (pintype "passive"))
      (node (ref "R70") (pin "2") (pintype "passive"))
      (node (ref "R72") (pin "1") (pintype "passive"))
      (node (ref "R74") (pin "1") (pintype "passive"))
      (node (ref "R75") (pin "2") (pintype "passive"))
      (node (ref "R77") (pin "1") (pintype "passive"))
      (node (ref "R79") (pin "1") (pintype "passive"))
      (node (ref "R8") (pin "1") (pintype "passive"))
      (node (ref "R83") (pin "1") (pintype "passive"))
      (node (ref "R85") (pin "1") (pintype "passive"))
      (node (ref "R87") (pin "1") (pintype "passive"))
      (node (ref "R89") (pin "1") (pintype "passive"))
      (node (ref "SD_CARD1") (pin "3") (pinfunction "VSS_3") (pintype "passive"))
      (node (ref "SD_CARD1") (pin "6") (pinfunction "VSS_6") (pintype "passive"))
      (node (ref "U1") (pin "107") (pinfunction "VSS_107") (pintype "passive"))
      (node (ref "U1") (pin "120") (pinfunction "VSS_120") (pintype "passive"))
      (node (ref "U1") (pin "130") (pinfunction "VSS_130") (pintype "passive"))
      (node (ref "U1") (pin "16") (pinfunction "VSS_16") (pintype "passive"))
      (node (ref "U1") (pin "31") (pinfunction "VSSA_31") (pintype "passive"))
      (node (ref "U1") (pin "38") (pinfunction "VSS_38") (pintype "passive"))
      (node (ref "U1") (pin "51") (pinfunction "VSS_51") (pintype "passive"))
      (node (ref "U1") (pin "61") (pinfunction "VSS_61") (pintype "passive"))
      (node (ref "U1") (pin "83") (pinfunction "VSS_83") (pintype "passive"))
      (node (ref "U1") (pin "94") (pinfunction "VSS_94") (pintype "passive"))
      (node (ref "U10") (pin "2") (pinfunction "GND_2") (pintype "power_in"))
      (node (ref "U10") (pin "8") (pinfunction "RS_8") (pintype "input"))
      (node (ref "U11") (pin "11") (pinfunction "GND_11") (pintype "passive"))
      (node (ref "U11") (pin "12") (pinfunction "GND_12") (pintype "passive"))
      (node (ref "U11") (pin "13") (pinfunction "GND_13") (pintype "passive"))
      (node (ref "U12") (pin "5") (pinfunction "AGND_5") (pintype "passive"))
      (node (ref "U13") (pin "5") (pinfunction "AGND_5") (pintype "passive"))
      (node (ref "U14") (pin "11") (pinfunction "GND_11") (pintype "passive"))
      (node (ref "U14") (pin "12") (pinfunction "GND_12") (pintype "passive"))
      (node (ref "U14") (pin "13") (pinfunction "GND_13") (pintype "passive"))
      (node (ref "U15") (pin "11") (pinfunction "GND_11") (pintype "passive"))
      (node (ref "U15") (pin "12") (pinfunction "GND_12") (pintype "passive"))
      (node (ref "U15") (pin "13") (pinfunction "GND_13") (pintype "passive"))
      (node (ref "U2") (pin "20") (pinfunction "PB2BOOT1_20") (pintype "passive"))
      (node (ref "U2") (pin "23") (pinfunction "VSS_1_23") (pintype "passive"))
      (node (ref "U2") (pin "35") (pinfunction "VSS_2_35") (pintype "passive"))
      (node (ref "U2") (pin "47") (pinfunction "VSS_3_47") (pintype "passive"))
      (node (ref "U2") (pin "8") (pinfunction "VSS_A_8") (pintype "passive"))
      (node (ref "U3") (pin "9") (pinfunction "GND_9") (pintype "passive"))
      (node (ref "U4") (pin "15") (pinfunction "GND_15") (pintype "passive"))
      (node (ref "U5") (pin "15") (pinfunction "GND_15") (pintype "passive"))
      (node (ref "U6") (pin "2") (pinfunction "GND_2") (pintype "passive"))
      (node (ref "U7") (pin "1") (pinfunction "GND_1") (pintype "passive"))
      (node (ref "U8") (pin "1") (pinfunction "GND_1") (pintype "passive"))
      (node (ref "U9") (pin "1") (pinfunction "GND_1") (pintype "passive"))
      (node (ref "USB1") (pin "1") (pinfunction "SH1_1") (pintype "passive"))
      (node (ref "USB1") (pin "2") (pinfunction "SH2_2") (pintype "passive"))
      (node (ref "USB1") (pin "3") (pinfunction "SH3_3") (pintype "passive"))
      (node (ref "USB1") (pin "4") (pinfunction "SH4_4") (pintype "passive"))
      (node (ref "USB1") (pin "A1") (pinfunction "GND_A1") (pintype "passive"))
      (node (ref "USB1") (pin "A12") (pinfunction "GND_A12") (pintype "passive"))
      (node (ref "USB1") (pin "B1") (pinfunction "GND_B1") (pintype "passive"))
      (node (ref "USB1") (pin "B12") (pinfunction "GND_B12") (pintype "passive"))
      (node (ref "USB2") (pin "1") (pinfunction "SH1_1") (pintype "passive"))
      (node (ref "USB2") (pin "2") (pinfunction "SH2_2") (pintype "passive"))
      (node (ref "USB2") (pin "3") (pinfunction "SH3_3") (pintype "passive"))
      (node (ref "USB2") (pin "4") (pinfunction "SH4_4") (pintype "passive"))
      (node (ref "USB2") (pin "A1") (pinfunction "GND_A1") (pintype "passive"))
      (node (ref "USB2") (pin "A12") (pinfunction "GND_A12") (pintype "passive"))
      (node (ref "USB2") (pin "B1") (pinfunction "GND_B1") (pintype "passive"))
      (node (ref "USB2") (pin "B12") (pinfunction "GND_B12") (pintype "passive"))
      (node (ref "Y2") (pin "2") (pinfunction "GND_2") (pintype "passive"))
      (node (ref "Y2") (pin "4") (pinfunction "GND_4") (pintype "passive"))
      (node (ref "Y3") (pin "2") (pinfunction "GND_2") (pintype "passive"))
      (node (ref "Y3") (pin "4") (pinfunction "GND_4") (pintype "passive"))
    )
    (net (code "180") (name "Net-(BAT1-VCC)") (class "Default")
      (node (ref "BAT1") (pin "1") (pinfunction "VCC_1") (pintype "passive"))
      (node (ref "D2") (pin "1") (pintype "passive"))
    )
    (net (code "181") (name "Net-(BEEP1-G)") (class "Default")
      (node (ref "BEEP1") (pin "2") (pinfunction "G_2") (pintype "passive"))
      (node (ref "Q2") (pin "3") (pinfunction "C_3") (pintype "passive"))
    )
    (net (code "182") (name "Net-(K2-COMMON)") (class "Default")
      (node (ref "K2") (pin "1") (pinfunction "COMMON_1") (pintype "passive"))
      (node (ref "P4") (pin "2") (pinfunction "2_2") (pintype "passive"))
    )
    (net (code "183") (name "Net-(K2-NC)") (class "Default")
      (node (ref "D3") (pin "1") (pintype "passive"))
      (node (ref "K2") (pin "2") (pinfunction "NC_2") (pintype "passive"))
    )
    (net (code "184") (name "Net-(LED1-K)") (class "Default")
      (node (ref "LED1") (pin "2") (pinfunction "K_2") (pintype "passive"))
      (node (ref "R20") (pin "1") (pintype "passive"))
    )
    (net (code "185") (name "Net-(LED2-K)") (class "Default")
      (node (ref "LED2") (pin "2") (pinfunction "K_2") (pintype "passive"))
      (node (ref "R21") (pin "1") (pintype "passive"))
    )
    (net (code "186") (name "Net-(LED3-K)") (class "Default")
      (node (ref "LED3") (pin "2") (pinfunction "K_2") (pintype "passive"))
      (node (ref "R29") (pin "1") (pintype "passive"))
    )
    (net (code "187") (name "Net-(LED4-K)") (class "Default")
      (node (ref "LED4") (pin "2") (pinfunction "K_2") (pintype "passive"))
      (node (ref "R30") (pin "1") (pintype "passive"))
    )
    (net (code "188") (name "Net-(LED5-A)") (class "Default")
      (node (ref "LED5") (pin "1") (pinfunction "A_1") (pintype "passive"))
      (node (ref "R36") (pin "1") (pintype "passive"))
    )
    (net (code "189") (name "Net-(LED6-A)") (class "Default")
      (node (ref "LED6") (pin "1") (pinfunction "A_1") (pintype "passive"))
      (node (ref "R37") (pin "1") (pintype "passive"))
    )
    (net (code "190") (name "Net-(LED7-A)") (class "Default")
      (node (ref "LED7") (pin "1") (pinfunction "A_1") (pintype "passive"))
      (node (ref "R39") (pin "1") (pintype "passive"))
    )
    (net (code "191") (name "Net-(LED8-A)") (class "Default")
      (node (ref "LED8") (pin "1") (pinfunction "A_1") (pintype "passive"))
      (node (ref "R40") (pin "1") (pintype "passive"))
    )
    (net (code "192") (name "Net-(LED9-A)") (class "Default")
      (node (ref "LED9") (pin "1") (pinfunction "A_1") (pintype "passive"))
      (node (ref "R41") (pin "1") (pintype "passive"))
    )
    (net (code "193") (name "Net-(LED10-A)") (class "Default")
      (node (ref "LED10") (pin "1") (pinfunction "A_1") (pintype "passive"))
      (node (ref "R42") (pin "1") (pintype "passive"))
    )
    (net (code "194") (name "Net-(LED11-A)") (class "Default")
      (node (ref "LED11") (pin "1") (pinfunction "A_1") (pintype "passive"))
      (node (ref "R43") (pin "1") (pintype "passive"))
    )
    (net (code "195") (name "Net-(LED12-A)") (class "Default")
      (node (ref "LED12") (pin "1") (pinfunction "A_1") (pintype "passive"))
      (node (ref "R44") (pin "1") (pintype "passive"))
    )
    (net (code "196") (name "Net-(LED13-A)") (class "Default")
      (node (ref "LED13") (pin "1") (pinfunction "A_1") (pintype "passive"))
      (node (ref "R45") (pin "1") (pintype "passive"))
    )
    (net (code "197") (name "Net-(LED14-A)") (class "Default")
      (node (ref "LED14") (pin "1") (pinfunction "A_1") (pintype "passive"))
      (node (ref "R46") (pin "1") (pintype "passive"))
    )
    (net (code "198") (name "Net-(OLED1-C1N)") (class "Default")
      (node (ref "C60") (pin "1") (pintype "passive"))
      (node (ref "OLED1") (pin "5") (pinfunction "C1N_5") (pintype "passive"))
    )
    (net (code "199") (name "Net-(OLED1-C1P)") (class "Default")
      (node (ref "C60") (pin "2") (pintype "passive"))
      (node (ref "OLED1") (pin "4") (pinfunction "C1P_4") (pintype "passive"))
    )
    (net (code "200") (name "Net-(OLED1-C2N)") (class "Default")
      (node (ref "C59") (pin "1") (pintype "passive"))
      (node (ref "OLED1") (pin "3") (pinfunction "C2N_3") (pintype "passive"))
    )
    (net (code "201") (name "Net-(OLED1-C2P)") (class "Default")
      (node (ref "C59") (pin "2") (pintype "passive"))
      (node (ref "OLED1") (pin "2") (pinfunction "C2P_2") (pintype "passive"))
    )
    (net (code "202") (name "Net-(OLED1-D2)") (class "Default")
      (node (ref "OLED1") (pin "20") (pinfunction "D2_20") (pintype "passive"))
      (node (ref "R58") (pin "2") (pintype "passive"))
    )
    (net (code "203") (name "Net-(OLED1-IREF)") (class "Default")
      (node (ref "OLED1") (pin "26") (pinfunction "IREF_26") (pintype "passive"))
      (node (ref "R57") (pin "2") (pintype "passive"))
    )
    (net (code "204") (name "Net-(OLED1-VCC)") (class "Default")
      (node (ref "C58") (pin "2") (pintype "passive"))
      (node (ref "OLED1") (pin "28") (pinfunction "VCC_28") (pintype "passive"))
    )
    (net (code "205") (name "Net-(OLED1-VCOMH)") (class "Default")
      (node (ref "C55") (pin "2") (pintype "passive"))
      (node (ref "OLED1") (pin "27") (pinfunction "VCOMH_27") (pintype "passive"))
    )
    (net (code "206") (name "Net-(P2-Pad3)") (class "Default")
      (node (ref "P2") (pin "3") (pinfunction "3_3") (pintype "passive"))
      (node (ref "R15") (pin "2") (pintype "passive"))
    )
    (net (code "207") (name "Net-(P2-Pad4)") (class "Default")
      (node (ref "P2") (pin "4") (pinfunction "4_4") (pintype "passive"))
      (node (ref "R23") (pin "1") (pintype "passive"))
    )
    (net (code "208") (name "Net-(Q1-B)") (class "Default")
      (node (ref "Q1") (pin "1") (pinfunction "B_1") (pintype "passive"))
      (node (ref "R3") (pin "1") (pintype "passive"))
      (node (ref "R5") (pin "2") (pintype "passive"))
      (node (ref "R6") (pin "1") (pintype "passive"))
    )
    (net (code "209") (name "Net-(Q1-E)") (class "Default")
      (node (ref "Q1") (pin "2") (pinfunction "E_2") (pintype "passive"))
      (node (ref "R9") (pin "2") (pintype "passive"))
    )
    (net (code "210") (name "Net-(Q2-B)") (class "Default")
      (node (ref "Q2") (pin "1") (pinfunction "B_1") (pintype "passive"))
      (node (ref "R27") (pin "1") (pintype "passive"))
    )
    (net (code "211") (name "Net-(Q2-E)") (class "Default")
      (node (ref "Q2") (pin "2") (pinfunction "E_2") (pintype "passive"))
      (node (ref "R28") (pin "1") (pintype "passive"))
    )
    (net (code "212") (name "Net-(U1-PH0-OSC_IN)") (class "Default")
      (node (ref "C12") (pin "1") (pintype "passive"))
      (node (ref "R19") (pin "2") (pintype "passive"))
      (node (ref "U1") (pin "23") (pinfunction "PH0-OSC_IN_23") (pintype "passive"))
      (node (ref "Y3") (pin "3") (pinfunction "OSC2_3") (pintype "passive"))
    )
    (net (code "213") (name "Net-(U1-PH1-OSC_OUT)") (class "Default")
      (node (ref "C13") (pin "2") (pintype "passive"))
      (node (ref "R19") (pin "1") (pintype "passive"))
      (node (ref "U1") (pin "24") (pinfunction "PH1-OSC_OUT_24") (pintype "passive"))
      (node (ref "Y3") (pin "1") (pinfunction "OSC1_1") (pintype "passive"))
    )
    (net (code "214") (name "Net-(U1-VDDA)") (class "Default")
      (node (ref "C10") (pin "2") (pintype "passive"))
      (node (ref "C11") (pin "2") (pintype "passive"))
      (node (ref "C14") (pin "2") (pintype "passive"))
      (node (ref "R22") (pin "1") (pintype "passive"))
      (node (ref "U1") (pin "32") (pinfunction "Vref+_32") (pintype "passive"))
      (node (ref "U1") (pin "33") (pinfunction "VDDA_33") (pintype "passive"))
    )
    (net (code "215") (name "Net-(U1-Vcap_1)") (class "Default")
      (node (ref "C8") (pin "2") (pintype "passive"))
      (node (ref "U1") (pin "71") (pinfunction "Vcap_1_71") (pintype "passive"))
    )
    (net (code "216") (name "Net-(U1-Vcap_2)") (class "Default")
      (node (ref "C9") (pin "2") (pintype "passive"))
      (node (ref "U1") (pin "106") (pinfunction "Vcap_2_106") (pintype "passive"))
    )
    (net (code "217") (name "Net-(U2-BOOT0)") (class "Default")
      (node (ref "R16") (pin "1") (pintype "passive"))
      (node (ref "U2") (pin "44") (pinfunction "BOOT0_44") (pintype "passive"))
    )
    (net (code "218") (name "Net-(U2-PB3JTDO)") (class "Default")
      (node (ref "R18") (pin "2") (pintype "passive"))
      (node (ref "U2") (pin "39") (pinfunction "PB3JTDO_39") (pintype "passive"))
    )
    (net (code "219") (name "Net-(U2-PB12SPI2_NSSI2C2_SMBAUSART3_CKTIM1_BKIN)") (class "Default")
      (node (ref "R17") (pin "2") (pintype "passive"))
      (node (ref "U2") (pin "25") (pinfunction "PB12SPI2_NSSI2C2_SMBAUSART3_CKTIM1_BKIN_25") (pintype "passive"))
    )
    (net (code "220") (name "Net-(U2-PC13-TAMPER-RTC)") (class "Default")
      (node (ref "R7") (pin "2") (pintype "passive"))
      (node (ref "U2") (pin "2") (pinfunction "PC13-TAMPER-RTC_2") (pintype "passive"))
    )
    (net (code "221") (name "Net-(U2-PC14-OSC32_IN)") (class "Default")
      (node (ref "R8") (pin "2") (pintype "passive"))
      (node (ref "U2") (pin "3") (pinfunction "PC14-OSC32_IN_3") (pintype "passive"))
    )
    (net (code "222") (name "Net-(U2-PD0-OSC_IN)") (class "Default")
      (node (ref "C1") (pin "2") (pintype "passive"))
      (node (ref "U2") (pin "5") (pinfunction "PD0-OSC_IN_5") (pintype "passive"))
      (node (ref "Y2") (pin "3") (pinfunction "OSC2_3") (pintype "passive"))
    )
    (net (code "223") (name "Net-(U2-PD1-OSC_OUT)") (class "Default")
      (node (ref "C2") (pin "1") (pintype "passive"))
      (node (ref "U2") (pin "6") (pinfunction "PD1-OSC_OUT_6") (pintype "passive"))
      (node (ref "Y2") (pin "1") (pinfunction "OSC1_1") (pintype "passive"))
    )
    (net (code "224") (name "Net-(U3-EN)") (class "Default")
      (node (ref "R26") (pin "1") (pintype "passive"))
      (node (ref "U3") (pin "3") (pinfunction "EN_3") (pintype "passive"))
    )
    (net (code "225") (name "Net-(U3-GPIO0)") (class "Default")
      (node (ref "R33") (pin "1") (pintype "passive"))
      (node (ref "U3") (pin "12") (pinfunction "GPIO0_12") (pintype "passive"))
    )
    (net (code "226") (name "Net-(U3-GPIO2)") (class "Default")
      (node (ref "R34") (pin "1") (pintype "passive"))
      (node (ref "U3") (pin "11") (pinfunction "GPIO2_11") (pintype "passive"))
    )
    (net (code "227") (name "Net-(U3-GPIO15)") (class "Default")
      (node (ref "R35") (pin "1") (pintype "passive"))
      (node (ref "U3") (pin "10") (pinfunction "GPIO15_10") (pintype "passive"))
    )
    (net (code "228") (name "Net-(U3-RST)") (class "Default")
      (node (ref "R25") (pin "1") (pintype "passive"))
      (node (ref "U3") (pin "1") (pinfunction "RST_1") (pintype "passive"))
    )
    (net (code "229") (name "Net-(U4-C1+)") (class "Default")
      (node (ref "C21") (pin "2") (pintype "passive"))
      (node (ref "U4") (pin "1") (pinfunction "C1+_1") (pintype "passive"))
    )
    (net (code "230") (name "Net-(U4-C1-)") (class "Default")
      (node (ref "C21") (pin "1") (pintype "passive"))
      (node (ref "U4") (pin "3") (pinfunction "C1-_3") (pintype "passive"))
    )
    (net (code "231") (name "Net-(U4-C2+)") (class "Default")
      (node (ref "C22") (pin "2") (pintype "passive"))
      (node (ref "U4") (pin "4") (pinfunction "C2+_4") (pintype "passive"))
    )
    (net (code "232") (name "Net-(U4-C2-)") (class "Default")
      (node (ref "C22") (pin "1") (pintype "passive"))
      (node (ref "U4") (pin "5") (pinfunction "C2-_5") (pintype "passive"))
    )
    (net (code "233") (name "Net-(U4-V+)") (class "Default")
      (node (ref "C16") (pin "2") (pintype "passive"))
      (node (ref "U4") (pin "2") (pinfunction "V+_2") (pintype "passive"))
    )
    (net (code "234") (name "Net-(U4-V-)") (class "Default")
      (node (ref "C17") (pin "2") (pintype "passive"))
      (node (ref "U4") (pin "6") (pinfunction "V-_6") (pintype "passive"))
    )
    (net (code "235") (name "Net-(U5-C1+)") (class "Default")
      (node (ref "C23") (pin "2") (pintype "passive"))
      (node (ref "U5") (pin "1") (pinfunction "C1+_1") (pintype "passive"))
    )
    (net (code "236") (name "Net-(U5-C1-)") (class "Default")
      (node (ref "C23") (pin "1") (pintype "passive"))
      (node (ref "U5") (pin "3") (pinfunction "C1-_3") (pintype "passive"))
    )
    (net (code "237") (name "Net-(U5-C2+)") (class "Default")
      (node (ref "C24") (pin "2") (pintype "passive"))
      (node (ref "U5") (pin "4") (pinfunction "C2+_4") (pintype "passive"))
    )
    (net (code "238") (name "Net-(U5-C2-)") (class "Default")
      (node (ref "C24") (pin "1") (pintype "passive"))
      (node (ref "U5") (pin "5") (pinfunction "C2-_5") (pintype "passive"))
    )
    (net (code "239") (name "Net-(U5-V+)") (class "Default")
      (node (ref "C18") (pin "2") (pintype "passive"))
      (node (ref "U5") (pin "2") (pinfunction "V+_2") (pintype "passive"))
    )
    (net (code "240") (name "Net-(U5-V-)") (class "Default")
      (node (ref "C19") (pin "2") (pintype "passive"))
      (node (ref "U5") (pin "6") (pinfunction "V-_6") (pintype "passive"))
    )
    (net (code "241") (name "Net-(U6-BST)") (class "Default")
      (node (ref "C33") (pin "1") (pintype "passive"))
      (node (ref "U6") (pin "1") (pinfunction "BST_1") (pintype "passive"))
    )
    (net (code "242") (name "Net-(U6-EN)") (class "Default")
      (node (ref "R32") (pin "1") (pintype "passive"))
      (node (ref "U6") (pin "4") (pinfunction "EN_4") (pintype "passive"))
    )
    (net (code "243") (name "Net-(U6-FB)") (class "Default")
      (node (ref "C39") (pin "1") (pintype "passive"))
      (node (ref "R38") (pin "1") (pintype "passive"))
      (node (ref "R47") (pin "2") (pintype "passive"))
      (node (ref "U6") (pin "3") (pinfunction "FB_3") (pintype "passive"))
    )
    (net (code "244") (name "Net-(U6-IN)") (class "Default")
      (node (ref "C27") (pin "2") (pintype "passive"))
      (node (ref "C30") (pin "2") (pintype "passive"))
      (node (ref "D3") (pin "2") (pintype "passive"))
      (node (ref "R32") (pin "2") (pintype "passive"))
      (node (ref "U6") (pin "5") (pinfunction "IN_5") (pintype "passive"))
    )
    (net (code "245") (name "Net-(U6-SW)") (class "Default")
      (node (ref "C33") (pin "2") (pintype "passive"))
      (node (ref "D4") (pin "2") (pintype "passive"))
      (node (ref "L1") (pin "2") (pintype "passive"))
      (node (ref "U6") (pin "6") (pinfunction "SW_6") (pintype "passive"))
    )
    (net (code "246") (name "Net-(U7-DTR#)") (class "Default")
      (node (ref "C34") (pin "2") (pintype "passive"))
      (node (ref "U7") (pin "13") (pinfunction "DTR#_13") (pintype "passive"))
    )
    (net (code "247") (name "Net-(U7-V3)") (class "Default")
      (node (ref "C41") (pin "1") (pintype "passive"))
      (node (ref "U7") (pin "4") (pinfunction "V3_4") (pintype "passive"))
    )
    (net (code "248") (name "Net-(U10-CANH)") (class "Default")
      (node (ref "P8") (pin "1") (pinfunction "1_1") (pintype "passive"))
      (node (ref "R59") (pin "2") (pintype "passive"))
      (node (ref "U10") (pin "7") (pinfunction "CANH_7") (pintype "bidirectional"))
    )
    (net (code "249") (name "Net-(U10-CANL)") (class "Default")
      (node (ref "P8") (pin "2") (pinfunction "2_2") (pintype "passive"))
      (node (ref "R59") (pin "1") (pintype "passive"))
      (node (ref "U10") (pin "6") (pinfunction "CANL_6") (pintype "bidirectional"))
    )
    (net (code "250") (name "Net-(U11-DIR)") (class "Default")
      (node (ref "R75") (pin "1") (pintype "passive"))
      (node (ref "U11") (pin "2") (pinfunction "DIR_2") (pintype "passive"))
    )
    (net (code "251") (name "Net-(U11-OE#)") (class "Default")
      (node (ref "R64") (pin "2") (pintype "passive"))
      (node (ref "U11") (pin "22") (pinfunction "OE#_22") (pintype "passive"))
    )
    (net (code "252") (name "Net-(U12-REFIN)") (class "Default")
      (node (ref "R76") (pin "1") (pintype "passive"))
      (node (ref "R77") (pin "2") (pintype "passive"))
      (node (ref "U12") (pin "6") (pinfunction "REFIN_6") (pintype "passive"))
    )
    (net (code "253") (name "Net-(U13-REFIN)") (class "Default")
      (node (ref "R78") (pin "1") (pintype "passive"))
      (node (ref "R79") (pin "2") (pintype "passive"))
      (node (ref "U13") (pin "6") (pinfunction "REFIN_6") (pintype "passive"))
    )
    (net (code "254") (name "Net-(U14-DIR)") (class "Default")
      (node (ref "R80") (pin "2") (pintype "passive"))
      (node (ref "U14") (pin "2") (pinfunction "DIR_2") (pintype "passive"))
    )
    (net (code "255") (name "Net-(U14-OE#)") (class "Default")
      (node (ref "R67") (pin "2") (pintype "passive"))
      (node (ref "U14") (pin "22") (pinfunction "OE#_22") (pintype "passive"))
    )
    (net (code "256") (name "Net-(U15-DIR)") (class "Default")
      (node (ref "R81") (pin "2") (pintype "passive"))
      (node (ref "U15") (pin "2") (pinfunction "DIR_2") (pintype "passive"))
    )
    (net (code "257") (name "Net-(U15-OE#)") (class "Default")
      (node (ref "R70") (pin "1") (pintype "passive"))
      (node (ref "U15") (pin "22") (pinfunction "OE#_22") (pintype "passive"))
    )
    (net (code "258") (name "Net-(USB1-CC1)") (class "Default")
      (node (ref "R10") (pin "2") (pintype "passive"))
      (node (ref "USB1") (pin "A5") (pinfunction "CC1_A5") (pintype "passive"))
    )
    (net (code "259") (name "Net-(USB1-CC2)") (class "Default")
      (node (ref "R11") (pin "1") (pintype "passive"))
      (node (ref "USB1") (pin "B5") (pinfunction "CC2_B5") (pintype "passive"))
    )
    (net (code "260") (name "Net-(USB2-CC1)") (class "Default")
      (node (ref "R24") (pin "2") (pintype "passive"))
      (node (ref "USB2") (pin "A5") (pinfunction "CC1_A5") (pintype "passive"))
    )
    (net (code "261") (name "Net-(USB2-CC2)") (class "Default")
      (node (ref "R31") (pin "1") (pintype "passive"))
      (node (ref "USB2") (pin "B5") (pinfunction "CC2_B5") (pintype "passive"))
    )
    (net (code "262") (name "ST_3.3V") (class "Default")
      (node (ref "C45") (pin "2") (pintype "passive"))
      (node (ref "C46") (pin "2") (pintype "passive"))
      (node (ref "C47") (pin "2") (pintype "passive"))
      (node (ref "C48") (pin "2") (pintype "passive"))
      (node (ref "D1") (pin "1") (pintype "passive"))
      (node (ref "P2") (pin "1") (pinfunction "1_1") (pintype "passive"))
      (node (ref "P2") (pin "2") (pinfunction "2_2") (pintype "passive"))
      (node (ref "R14") (pin "1") (pintype "passive"))
      (node (ref "R22") (pin "2") (pintype "passive"))
      (node (ref "R61") (pin "2") (pintype "passive"))
      (node (ref "R62") (pin "2") (pintype "passive"))
      (node (ref "U1") (pin "108") (pinfunction "VDD_108") (pintype "passive"))
      (node (ref "U1") (pin "121") (pinfunction "VDD_121") (pintype "passive"))
      (node (ref "U1") (pin "131") (pinfunction "VDD_131") (pintype "passive"))
      (node (ref "U1") (pin "144") (pinfunction "VDD_144") (pintype "passive"))
      (node (ref "U1") (pin "17") (pinfunction "VDD_17") (pintype "passive"))
      (node (ref "U1") (pin "30") (pinfunction "VDD_30") (pintype "passive"))
      (node (ref "U1") (pin "39") (pinfunction "VDD_39") (pintype "passive"))
      (node (ref "U1") (pin "52") (pinfunction "VDD_52") (pintype "passive"))
      (node (ref "U1") (pin "62") (pinfunction "VDD_62") (pintype "passive"))
      (node (ref "U1") (pin "72") (pinfunction "VDD_72") (pintype "passive"))
      (node (ref "U1") (pin "84") (pinfunction "VDD_84") (pintype "passive"))
      (node (ref "U1") (pin "95") (pinfunction "VDD_95") (pintype "passive"))
    )
    (net (code "263") (name "STp_3.3V") (class "Default")
      (node (ref "C52") (pin "2") (pintype "passive"))
      (node (ref "C53") (pin "2") (pintype "passive"))
      (node (ref "LED1") (pin "1") (pinfunction "A_1") (pintype "passive"))
      (node (ref "LED2") (pin "1") (pinfunction "A_1") (pintype "passive"))
      (node (ref "P3") (pin "1") (pinfunction "1_1") (pintype "passive"))
      (node (ref "Q1") (pin "3") (pinfunction "C_3") (pintype "passive"))
      (node (ref "R1") (pin "2") (pintype "passive"))
      (node (ref "R18") (pin "1") (pintype "passive"))
      (node (ref "R4") (pin "2") (pintype "passive"))
      (node (ref "R63") (pin "2") (pintype "passive"))
      (node (ref "U2") (pin "1") (pinfunction "VBAT_1") (pintype "passive"))
      (node (ref "U2") (pin "24") (pinfunction "VDD_1_24") (pintype "passive"))
      (node (ref "U2") (pin "36") (pinfunction "VDD_2_36") (pintype "passive"))
      (node (ref "U2") (pin "48") (pinfunction "VDD_3_48") (pintype "passive"))
      (node (ref "U2") (pin "9") (pinfunction "VDD_A_9") (pintype "passive"))
    )
    (net (code "264") (name "VBUS") (class "Default")
      (node (ref "C15") (pin "2") (pintype "passive"))
      (node (ref "C20") (pin "2") (pintype "passive"))
      (node (ref "F1") (pin "1") (pinfunction "1_1") (pintype "passive"))
      (node (ref "USB1") (pin "A4") (pinfunction "VBUS_A4") (pintype "passive"))
      (node (ref "USB1") (pin "A9") (pinfunction "VBUS_A9") (pintype "passive"))
      (node (ref "USB1") (pin "B4") (pinfunction "VBUS_B4") (pintype "passive"))
      (node (ref "USB1") (pin "B9") (pinfunction "VBUS_B9") (pintype "passive"))
      (node (ref "USB2") (pin "A4") (pinfunction "VBUS_A4") (pintype "passive"))
      (node (ref "USB2") (pin "A9") (pinfunction "VBUS_A9") (pintype "passive"))
      (node (ref "USB2") (pin "B4") (pinfunction "VBUS_B4") (pintype "passive"))
      (node (ref "USB2") (pin "B9") (pinfunction "VBUS_B9") (pintype "passive"))
    )
    (net (code "265") (name "unconnected-(K2-NO-Pad3)") (class "Default")
      (node (ref "K2") (pin "3") (pinfunction "NO_3") (pintype "passive"))
    )
    (net (code "266") (name "unconnected-(OLED1-NC(VBREF)-Pad7)") (class "Default")
      (node (ref "OLED1") (pin "7") (pinfunction "NC(VBREF)_7") (pintype "passive"))
    )
    (net (code "267") (name "unconnected-(P5-Pad1)") (class "Default")
      (node (ref "P5") (pin "1") (pinfunction "1_1") (pintype "passive"))
    )
    (net (code "268") (name "unconnected-(P5-Pad4)") (class "Default")
      (node (ref "P5") (pin "4") (pinfunction "4_4") (pintype "passive"))
    )
    (net (code "269") (name "unconnected-(P5-Pad6)") (class "Default")
      (node (ref "P5") (pin "6") (pinfunction "6_6") (pintype "passive"))
    )
    (net (code "270") (name "unconnected-(P5-Pad7)") (class "Default")
      (node (ref "P5") (pin "7") (pinfunction "7_7") (pintype "passive"))
    )
    (net (code "271") (name "unconnected-(P5-Pad8)") (class "Default")
      (node (ref "P5") (pin "8") (pinfunction "8_8") (pintype "passive"))
    )
    (net (code "272") (name "unconnected-(P5-Pad9)") (class "Default")
      (node (ref "P5") (pin "9") (pinfunction "9_9") (pintype "passive"))
    )
    (net (code "273") (name "unconnected-(P6-Pad1)") (class "Default")
      (node (ref "P6") (pin "1") (pinfunction "1_1") (pintype "passive"))
    )
    (net (code "274") (name "unconnected-(P6-Pad4)") (class "Default")
      (node (ref "P6") (pin "4") (pinfunction "4_4") (pintype "passive"))
    )
    (net (code "275") (name "unconnected-(P6-Pad6)") (class "Default")
      (node (ref "P6") (pin "6") (pinfunction "6_6") (pintype "passive"))
    )
    (net (code "276") (name "unconnected-(P6-Pad7)") (class "Default")
      (node (ref "P6") (pin "7") (pinfunction "7_7") (pintype "passive"))
    )
    (net (code "277") (name "unconnected-(P6-Pad8)") (class "Default")
      (node (ref "P6") (pin "8") (pinfunction "8_8") (pintype "passive"))
    )
    (net (code "278") (name "unconnected-(P6-Pad9)") (class "Default")
      (node (ref "P6") (pin "9") (pinfunction "9_9") (pintype "passive"))
    )
    (net (code "279") (name "unconnected-(P7-Pad1)") (class "Default")
      (node (ref "P7") (pin "1") (pinfunction "1_1") (pintype "passive"))
    )
    (net (code "280") (name "unconnected-(P7-Pad4)") (class "Default")
      (node (ref "P7") (pin "4") (pinfunction "4_4") (pintype "passive"))
    )
    (net (code "281") (name "unconnected-(P7-Pad6)") (class "Default")
      (node (ref "P7") (pin "6") (pinfunction "6_6") (pintype "passive"))
    )
    (net (code "282") (name "unconnected-(P7-Pad7)") (class "Default")
      (node (ref "P7") (pin "7") (pinfunction "7_7") (pintype "passive"))
    )
    (net (code "283") (name "unconnected-(P7-Pad8)") (class "Default")
      (node (ref "P7") (pin "8") (pinfunction "8_8") (pintype "passive"))
    )
    (net (code "284") (name "unconnected-(P7-Pad9)") (class "Default")
      (node (ref "P7") (pin "9") (pinfunction "9_9") (pintype "passive"))
    )
    (net (code "285") (name "unconnected-(SD_CARD1-CD-Pad10)") (class "Default")
      (node (ref "SD_CARD1") (pin "10") (pinfunction "CD_10") (pintype "passive"))
    )
    (net (code "286") (name "unconnected-(SD_CARD1-GND-Pad11)") (class "Default")
      (node (ref "SD_CARD1") (pin "11") (pinfunction "GND_11") (pintype "passive"))
    )
    (net (code "287") (name "unconnected-(SD_CARD1-WP-Pad12)") (class "Default")
      (node (ref "SD_CARD1") (pin "12") (pinfunction "WP_12") (pintype "passive"))
    )
    (net (code "288") (name "unconnected-(U1-PDR_ON-Pad143)") (class "Default")
      (node (ref "U1") (pin "143") (pinfunction "PDR_ON_143") (pintype "passive"))
    )
    (net (code "289") (name "unconnected-(U2-PA1USART2_RTSADC12_IN1TIM2_CH2-Pad11)") (class "Default")
      (node (ref "U2") (pin "11") (pinfunction "PA1USART2_RTSADC12_IN1TIM2_CH2_11") (pintype "passive"))
    )
    (net (code "290") (name "unconnected-(U2-PA4SPI1_NSSUSART2_CKADC12_IN4-Pad14)") (class "Default")
      (node (ref "U2") (pin "14") (pinfunction "PA4SPI1_NSSUSART2_CKADC12_IN4_14") (pintype "passive"))
    )
    (net (code "291") (name "unconnected-(U2-PA6SPI1_MISOADC12_IN6TIM3_CH1-Pad16)") (class "Default")
      (node (ref "U2") (pin "16") (pinfunction "PA6SPI1_MISOADC12_IN6TIM3_CH1_16") (pintype "passive"))
    )
    (net (code "292") (name "unconnected-(U2-PA7SPI1_MOSIADC12_IN7TIM3_CH2-Pad17)") (class "Default")
      (node (ref "U2") (pin "17") (pinfunction "PA7SPI1_MOSIADC12_IN7TIM3_CH2_17") (pintype "passive"))
    )
    (net (code "293") (name "unconnected-(U2-PA8USART1_CKTIM1_CH1MCO-Pad29)") (class "Default")
      (node (ref "U2") (pin "29") (pinfunction "PA8USART1_CKTIM1_CH1MCO_29") (pintype "passive"))
    )
    (net (code "294") (name "unconnected-(U2-PA10USART1_RXTIM1_CH3-Pad31)") (class "Default")
      (node (ref "U2") (pin "31") (pinfunction "PA10USART1_RXTIM1_CH3_31") (pintype "passive"))
    )
    (net (code "295") (name "unconnected-(U2-PB1ADC12_IN9TIM3_CH4-Pad19)") (class "Default")
      (node (ref "U2") (pin "19") (pinfunction "PB1ADC12_IN9TIM3_CH4_19") (pintype "passive"))
    )
    (net (code "296") (name "unconnected-(U2-PB4NJTRST-Pad40)") (class "Default")
      (node (ref "U2") (pin "40") (pinfunction "PB4NJTRST_40") (pintype "passive"))
    )
    (net (code "297") (name "unconnected-(U2-PB5I2C1_SMBA-Pad41)") (class "Default")
      (node (ref "U2") (pin "41") (pinfunction "PB5I2C1_SMBA_41") (pintype "passive"))
    )
    (net (code "298") (name "unconnected-(U2-PB6I2C1_SCLTIM4_CH1-Pad42)") (class "Default")
      (node (ref "U2") (pin "42") (pinfunction "PB6I2C1_SCLTIM4_CH1_42") (pintype "passive"))
    )
    (net (code "299") (name "unconnected-(U2-PB7I2C1_SDATIM4_CH2-Pad43)") (class "Default")
      (node (ref "U2") (pin "43") (pinfunction "PB7I2C1_SDATIM4_CH2_43") (pintype "passive"))
    )
    (net (code "300") (name "unconnected-(U2-PB8TIM4_CH3-Pad45)") (class "Default")
      (node (ref "U2") (pin "45") (pinfunction "PB8TIM4_CH3_45") (pintype "passive"))
    )
    (net (code "301") (name "unconnected-(U2-PB9TIM4_CH4-Pad46)") (class "Default")
      (node (ref "U2") (pin "46") (pinfunction "PB9TIM4_CH4_46") (pintype "passive"))
    )
    (net (code "302") (name "unconnected-(U2-PB10I2C2_SCLUSART3_TX-Pad21)") (class "Default")
      (node (ref "U2") (pin "21") (pinfunction "PB10I2C2_SCLUSART3_TX_21") (pintype "passive"))
    )
    (net (code "303") (name "unconnected-(U2-PB11I2C2_SDAUSART3_RX--Pad22)") (class "Default")
      (node (ref "U2") (pin "22") (pinfunction "PB11I2C2_SDAUSART3_RX-_22") (pintype "passive"))
    )
    (net (code "304") (name "unconnected-(U2-PB15SPI2_MOSITIM1_CH3N-Pad28)") (class "Default")
      (node (ref "U2") (pin "28") (pinfunction "PB15SPI2_MOSITIM1_CH3N_28") (pintype "passive"))
    )
    (net (code "305") (name "unconnected-(U2-PC15-OSC32_OUT-Pad4)") (class "Default")
      (node (ref "U2") (pin "4") (pinfunction "PC15-OSC32_OUT_4") (pintype "passive"))
    )
    (net (code "306") (name "unconnected-(U3-ADC-Pad2)") (class "Default")
      (node (ref "U3") (pin "2") (pinfunction "ADC_2") (pintype "passive"))
    )
    (net (code "307") (name "unconnected-(U3-CS0-Pad17)") (class "Default")
      (node (ref "U3") (pin "17") (pinfunction "CS0_17") (pintype "passive"))
    )
    (net (code "308") (name "unconnected-(U3-GPIO4-Pad13)") (class "Default")
      (node (ref "U3") (pin "13") (pinfunction "GPIO4_13") (pintype "passive"))
    )
    (net (code "309") (name "unconnected-(U3-GPIO5-Pad14)") (class "Default")
      (node (ref "U3") (pin "14") (pinfunction "GPIO5_14") (pintype "passive"))
    )
    (net (code "310") (name "unconnected-(U3-GPIO9-Pad19)") (class "Default")
      (node (ref "U3") (pin "19") (pinfunction "GPIO9_19") (pintype "passive"))
    )
    (net (code "311") (name "unconnected-(U3-GPIO10-Pad20)") (class "Default")
      (node (ref "U3") (pin "20") (pinfunction "GPIO10_20") (pintype "passive"))
    )
    (net (code "312") (name "unconnected-(U3-GPIO12-Pad6)") (class "Default")
      (node (ref "U3") (pin "6") (pinfunction "GPIO12_6") (pintype "passive"))
    )
    (net (code "313") (name "unconnected-(U3-GPIO13-Pad7)") (class "Default")
      (node (ref "U3") (pin "7") (pinfunction "GPIO13_7") (pintype "passive"))
    )
    (net (code "314") (name "unconnected-(U3-GPIO14-Pad5)") (class "Default")
      (node (ref "U3") (pin "5") (pinfunction "GPIO14_5") (pintype "passive"))
    )
    (net (code "315") (name "unconnected-(U3-GPIO16-Pad4)") (class "Default")
      (node (ref "U3") (pin "4") (pinfunction "GPIO16_4") (pintype "passive"))
    )
    (net (code "316") (name "unconnected-(U3-MISO-Pad18)") (class "Default")
      (node (ref "U3") (pin "18") (pinfunction "MISO_18") (pintype "passive"))
    )
    (net (code "317") (name "unconnected-(U3-MOSI-Pad21)") (class "Default")
      (node (ref "U3") (pin "21") (pinfunction "MOSI_21") (pintype "passive"))
    )
    (net (code "318") (name "unconnected-(U3-SCLK-Pad22)") (class "Default")
      (node (ref "U3") (pin "22") (pinfunction "SCLK_22") (pintype "passive"))
    )
    (net (code "319") (name "unconnected-(U5-R2IN-Pad8)") (class "Default")
      (node (ref "U5") (pin "8") (pinfunction "R2IN_8") (pintype "passive"))
    )
    (net (code "320") (name "unconnected-(U5-R2OUT-Pad9)") (class "Default")
      (node (ref "U5") (pin "9") (pinfunction "R2OUT_9") (pintype "passive"))
    )
    (net (code "321") (name "unconnected-(U5-T2IN-Pad10)") (class "Default")
      (node (ref "U5") (pin "10") (pinfunction "T2IN_10") (pintype "passive"))
    )
    (net (code "322") (name "unconnected-(U5-T2OUT-Pad7)") (class "Default")
      (node (ref "U5") (pin "7") (pinfunction "T2OUT_7") (pintype "passive"))
    )
    (net (code "323") (name "unconnected-(U7-CTS#-Pad9)") (class "Default")
      (node (ref "U7") (pin "9") (pinfunction "CTS#_9") (pintype "passive+no_connect"))
    )
    (net (code "324") (name "unconnected-(U7-DCD#-Pad12)") (class "Default")
      (node (ref "U7") (pin "12") (pinfunction "DCD#_12") (pintype "passive+no_connect"))
    )
    (net (code "325") (name "unconnected-(U7-DSR#-Pad10)") (class "Default")
      (node (ref "U7") (pin "10") (pinfunction "DSR#_10") (pintype "passive+no_connect"))
    )
    (net (code "326") (name "unconnected-(U7-R232-Pad15)") (class "Default")
      (node (ref "U7") (pin "15") (pinfunction "R232_15") (pintype "passive+no_connect"))
    )
    (net (code "327") (name "unconnected-(U7-RI#-Pad11)") (class "Default")
      (node (ref "U7") (pin "11") (pinfunction "RI#_11") (pintype "passive+no_connect"))
    )
    (net (code "328") (name "unconnected-(U7-RTS#-Pad14)") (class "Default")
      (node (ref "U7") (pin "14") (pinfunction "RTS#_14") (pintype "passive+no_connect"))
    )
    (net (code "329") (name "unconnected-(U7-XI-Pad7)") (class "Default")
      (node (ref "U7") (pin "7") (pinfunction "XI_7") (pintype "passive+no_connect"))
    )
    (net (code "330") (name "unconnected-(U7-XO-Pad8)") (class "Default")
      (node (ref "U7") (pin "8") (pinfunction "XO_8") (pintype "passive+no_connect"))
    )
    (net (code "331") (name "unconnected-(U10-Vref-Pad5)") (class "Default")
      (node (ref "U10") (pin "5") (pinfunction "Vref_5") (pintype "output"))
    )
    (net (code "332") (name "unconnected-(U11-A7-Pad9)") (class "Default")
      (node (ref "U11") (pin "9") (pinfunction "A7_9") (pintype "passive"))
    )
    (net (code "333") (name "unconnected-(U11-A8-Pad10)") (class "Default")
      (node (ref "U11") (pin "10") (pinfunction "A8_10") (pintype "passive"))
    )
    (net (code "334") (name "unconnected-(U11-B7-Pad15)") (class "Default")
      (node (ref "U11") (pin "15") (pinfunction "B7_15") (pintype "passive"))
    )
    (net (code "335") (name "unconnected-(U11-B8-Pad14)") (class "Default")
      (node (ref "U11") (pin "14") (pinfunction "B8_14") (pintype "passive"))
    )
    (net (code "336") (name "unconnected-(USB1-RX1+-PadB11)") (class "Default")
      (node (ref "USB1") (pin "B11") (pinfunction "RX1+_B11") (pintype "passive"))
    )
    (net (code "337") (name "unconnected-(USB1-RX1--PadB10)") (class "Default")
      (node (ref "USB1") (pin "B10") (pinfunction "RX1-_B10") (pintype "passive"))
    )
    (net (code "338") (name "unconnected-(USB1-RX2+-PadA11)") (class "Default")
      (node (ref "USB1") (pin "A11") (pinfunction "RX2+_A11") (pintype "passive"))
    )
    (net (code "339") (name "unconnected-(USB1-RX2--PadA10)") (class "Default")
      (node (ref "USB1") (pin "A10") (pinfunction "RX2-_A10") (pintype "passive"))
    )
    (net (code "340") (name "unconnected-(USB1-SBU1-PadA8)") (class "Default")
      (node (ref "USB1") (pin "A8") (pinfunction "SBU1_A8") (pintype "passive"))
    )
    (net (code "341") (name "unconnected-(USB1-SBU2-PadB8)") (class "Default")
      (node (ref "USB1") (pin "B8") (pinfunction "SBU2_B8") (pintype "passive"))
    )
    (net (code "342") (name "unconnected-(USB1-TX1+-PadA2)") (class "Default")
      (node (ref "USB1") (pin "A2") (pinfunction "TX1+_A2") (pintype "passive"))
    )
    (net (code "343") (name "unconnected-(USB1-TX1--PadA3)") (class "Default")
      (node (ref "USB1") (pin "A3") (pinfunction "TX1-_A3") (pintype "passive"))
    )
    (net (code "344") (name "unconnected-(USB1-TX2+-PadB2)") (class "Default")
      (node (ref "USB1") (pin "B2") (pinfunction "TX2+_B2") (pintype "passive"))
    )
    (net (code "345") (name "unconnected-(USB1-TX2--PadB3)") (class "Default")
      (node (ref "USB1") (pin "B3") (pinfunction "TX2-_B3") (pintype "passive"))
    )
    (net (code "346") (name "unconnected-(USB2-RX1+-PadB11)") (class "Default")
      (node (ref "USB2") (pin "B11") (pinfunction "RX1+_B11") (pintype "passive"))
    )
    (net (code "347") (name "unconnected-(USB2-RX1--PadB10)") (class "Default")
      (node (ref "USB2") (pin "B10") (pinfunction "RX1-_B10") (pintype "passive"))
    )
    (net (code "348") (name "unconnected-(USB2-RX2+-PadA11)") (class "Default")
      (node (ref "USB2") (pin "A11") (pinfunction "RX2+_A11") (pintype "passive"))
    )
    (net (code "349") (name "unconnected-(USB2-RX2--PadA10)") (class "Default")
      (node (ref "USB2") (pin "A10") (pinfunction "RX2-_A10") (pintype "passive"))
    )
    (net (code "350") (name "unconnected-(USB2-SBU1-PadA8)") (class "Default")
      (node (ref "USB2") (pin "A8") (pinfunction "SBU1_A8") (pintype "passive"))
    )
    (net (code "351") (name "unconnected-(USB2-SBU2-PadB8)") (class "Default")
      (node (ref "USB2") (pin "B8") (pinfunction "SBU2_B8") (pintype "passive"))
    )
    (net (code "352") (name "unconnected-(USB2-TX1+-PadA2)") (class "Default")
      (node (ref "USB2") (pin "A2") (pinfunction "TX1+_A2") (pintype "passive"))
    )
    (net (code "353") (name "unconnected-(USB2-TX1--PadA3)") (class "Default")
      (node (ref "USB2") (pin "A3") (pinfunction "TX1-_A3") (pintype "passive"))
    )
    (net (code "354") (name "unconnected-(USB2-TX2+-PadB2)") (class "Default")
      (node (ref "USB2") (pin "B2") (pinfunction "TX2+_B2") (pintype "passive"))
    )
    (net (code "355") (name "unconnected-(USB2-TX2--PadB3)") (class "Default")
      (node (ref "USB2") (pin "B3") (pinfunction "TX2-_B3") (pintype "passive"))
    )
  )
)
